# OpenTherm_Board_77X.net
KiCad netlist of a schematic drawn in EAGLE
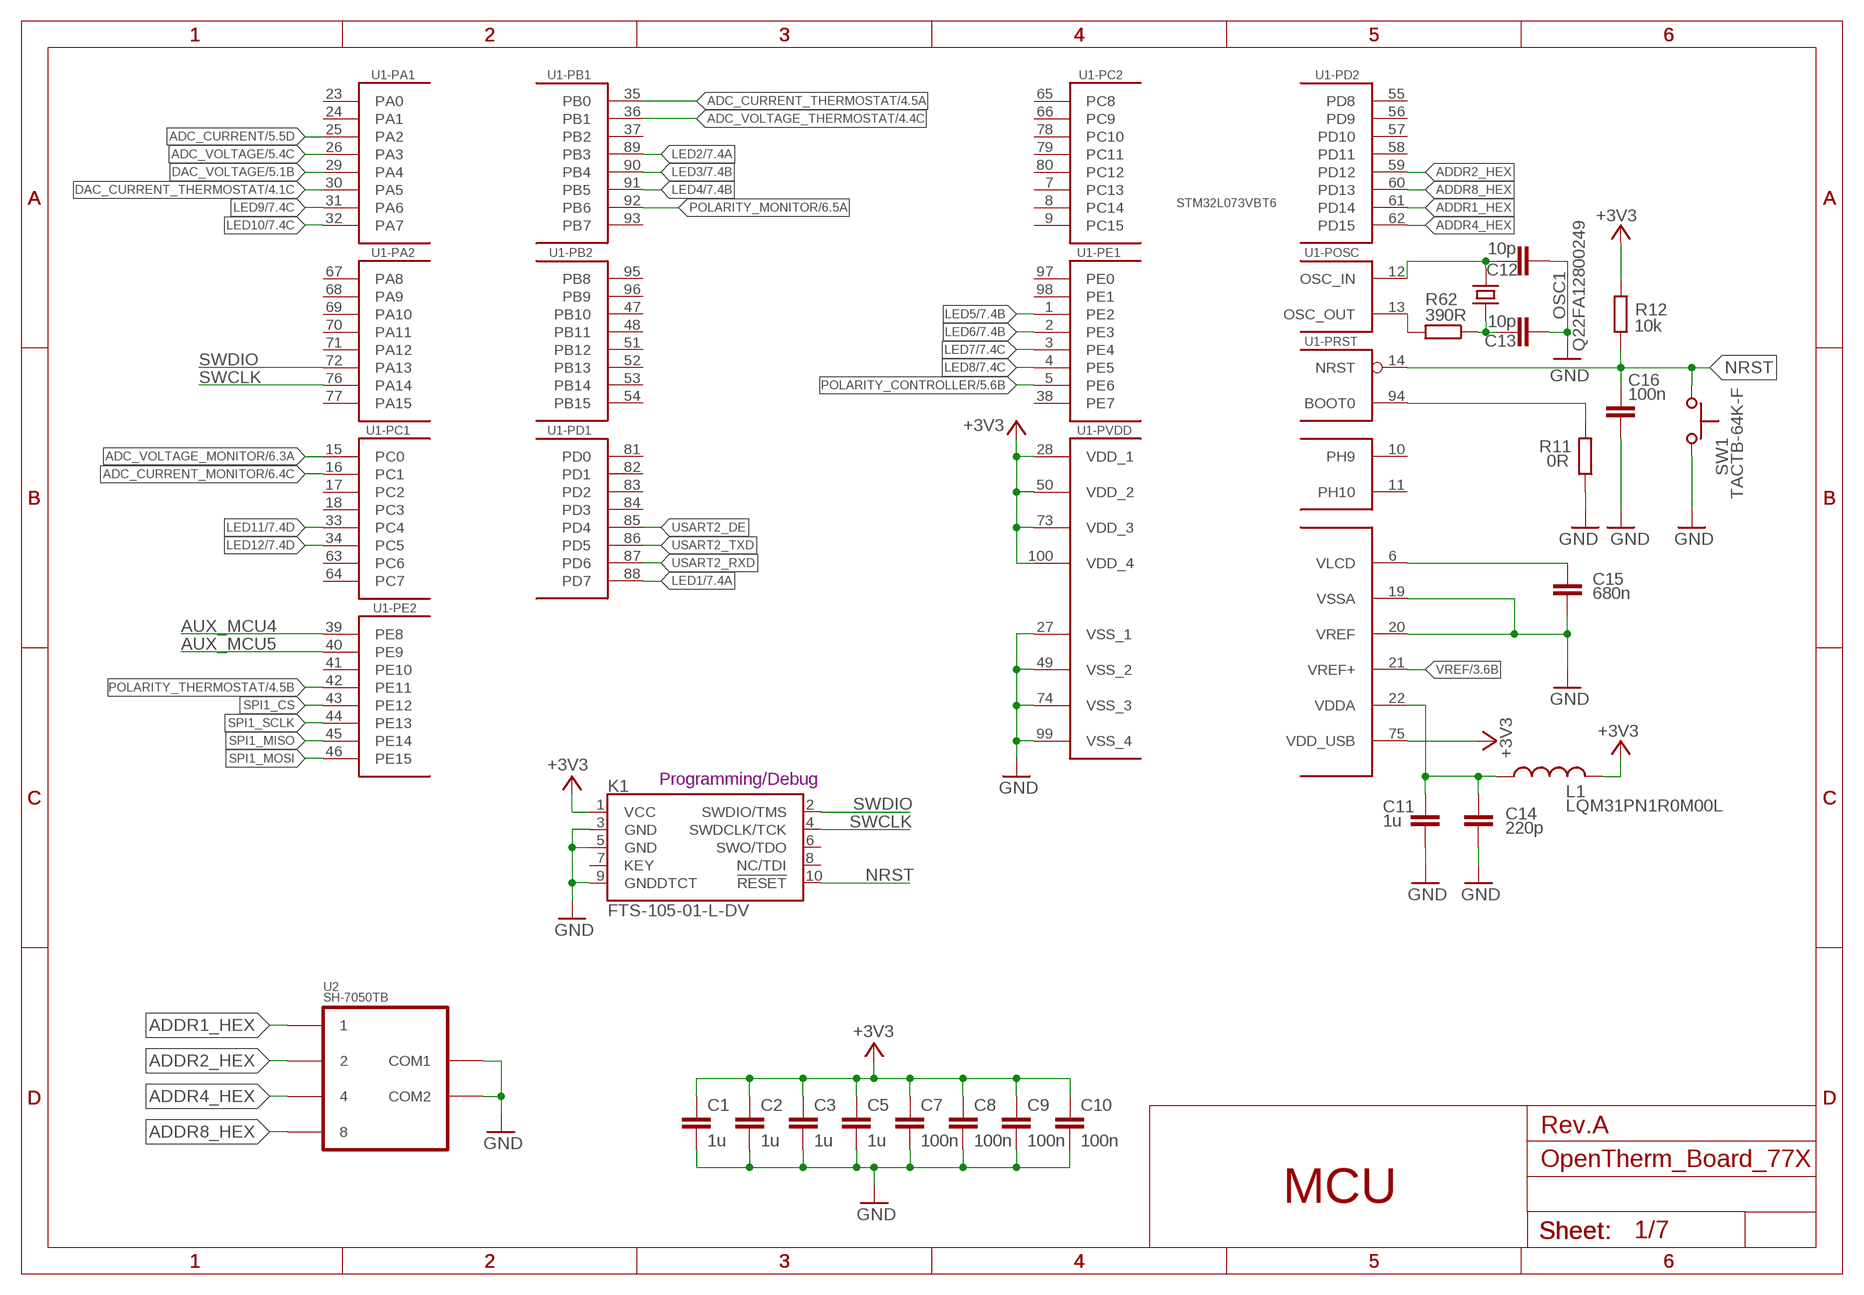
[diagram p0: schematic, sheet 1]
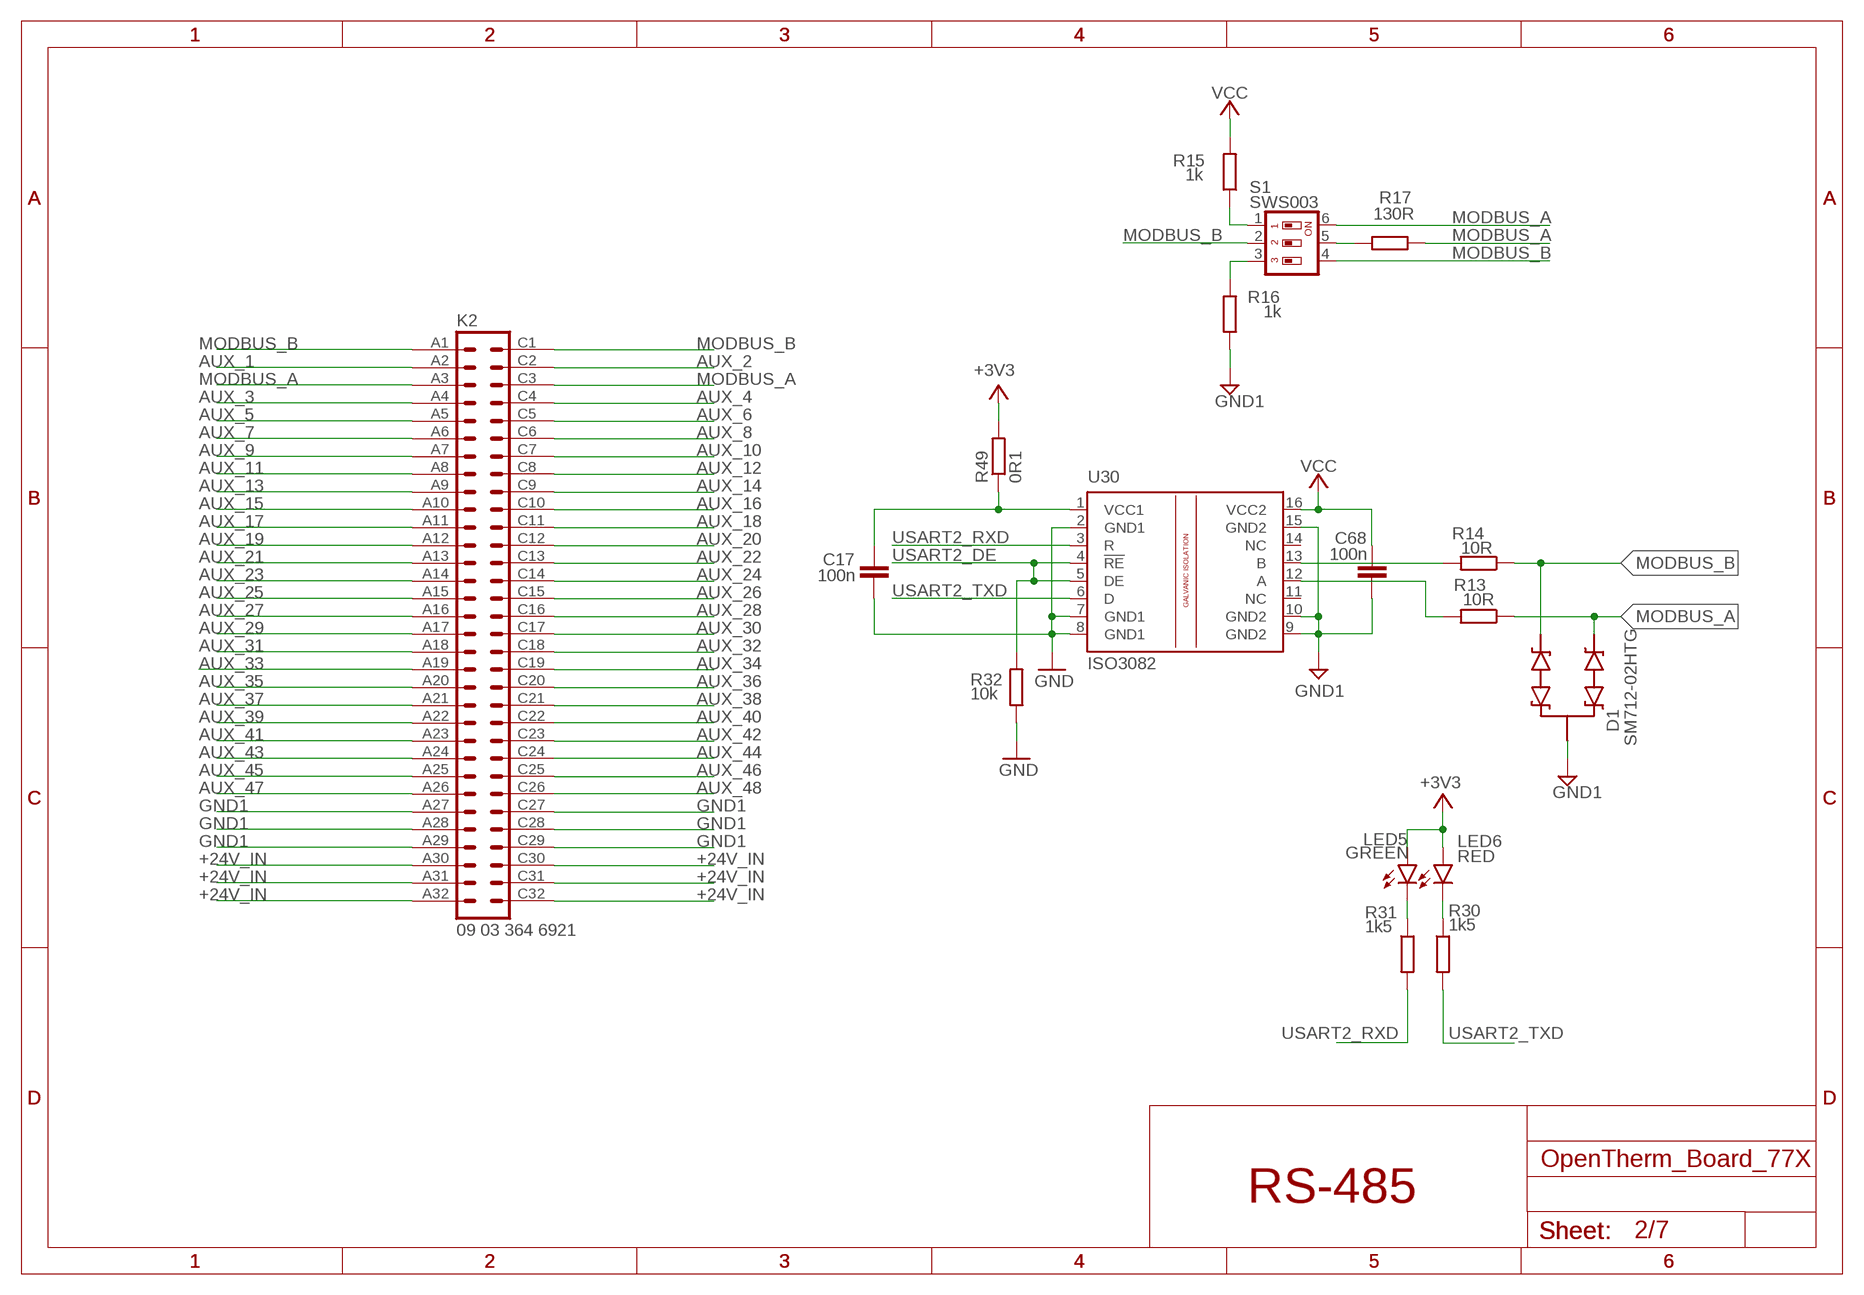
[diagram p1: schematic, sheet 2]
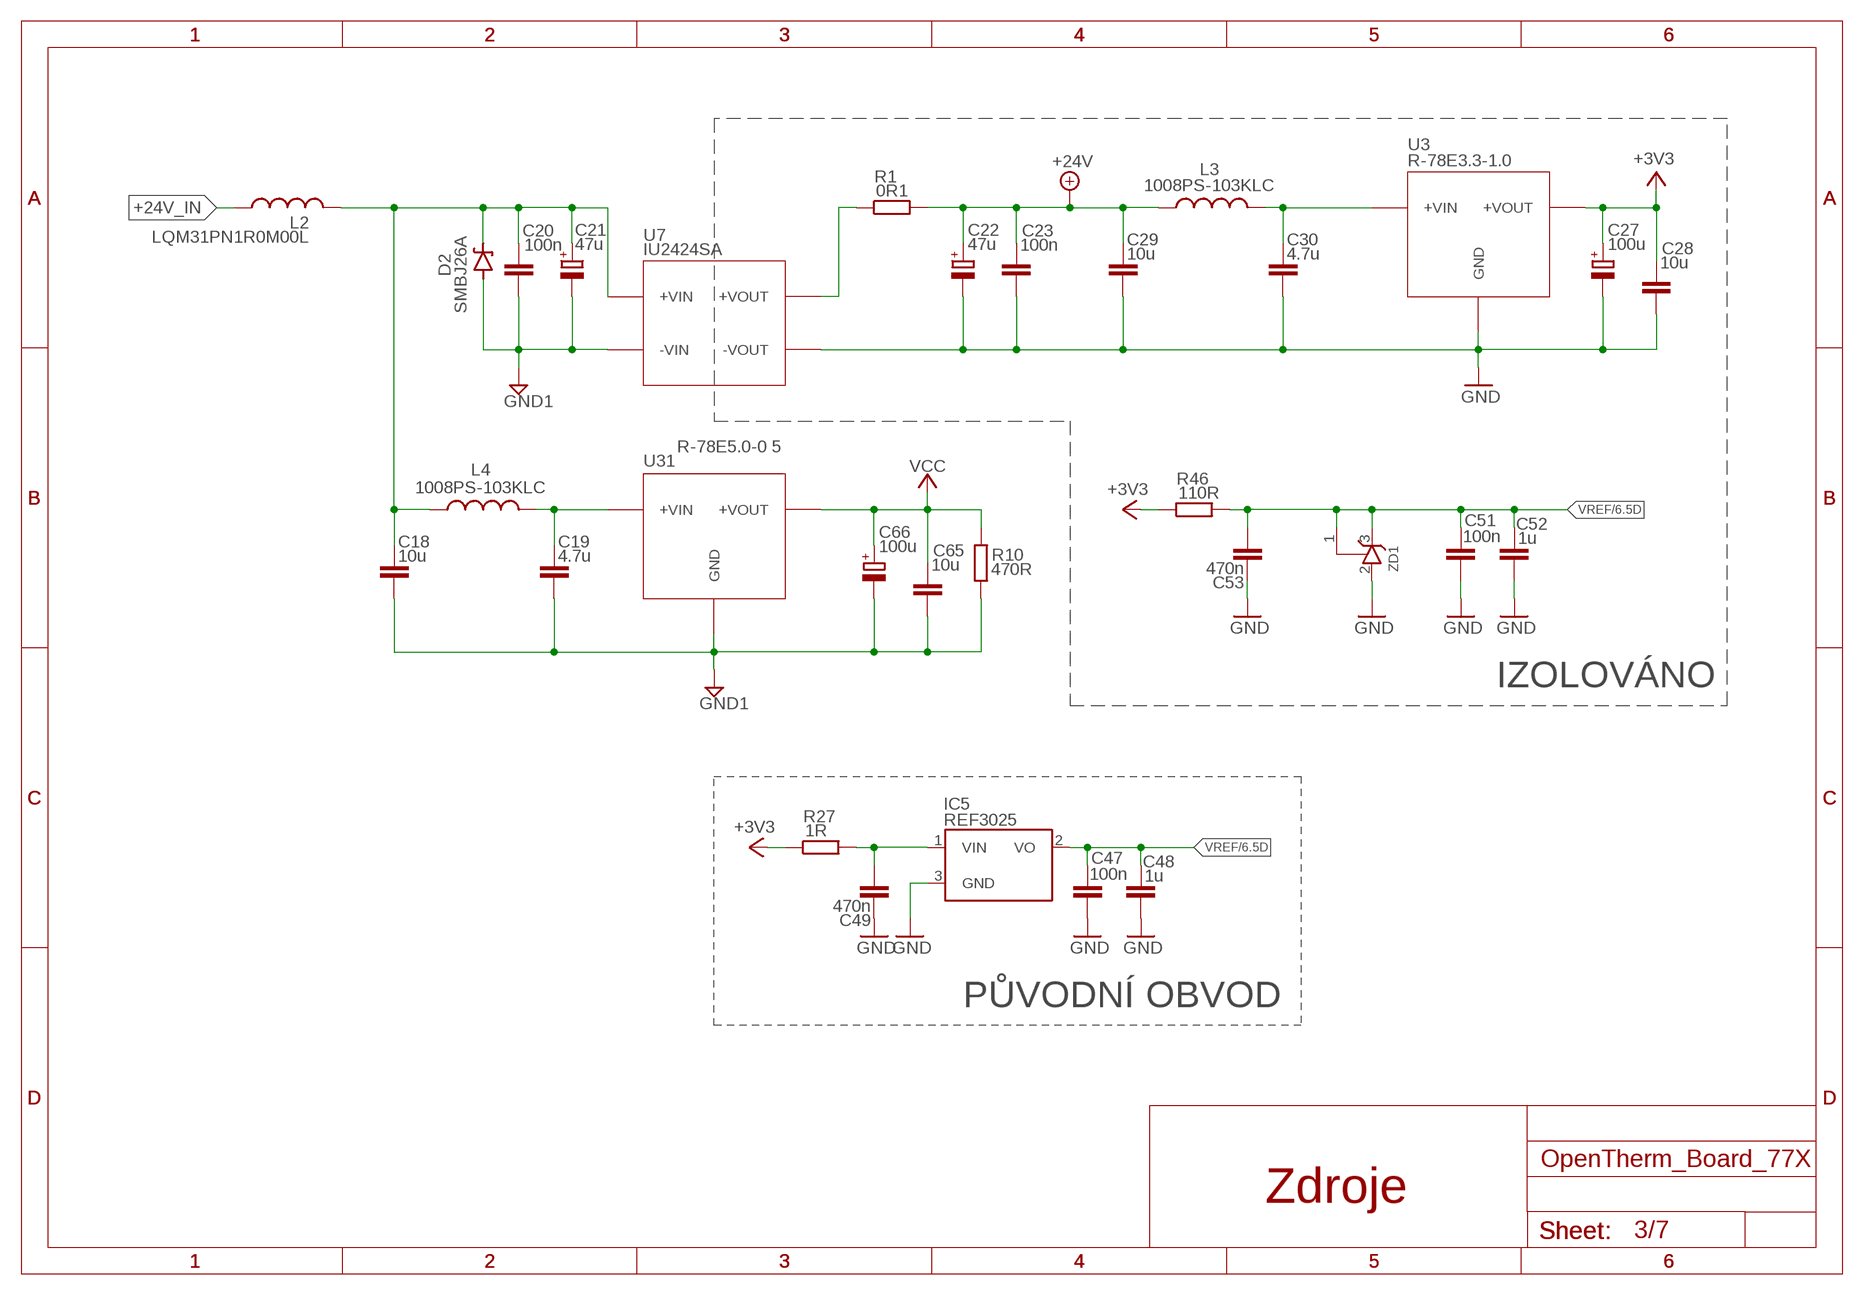
[diagram p2: schematic, sheet 3]
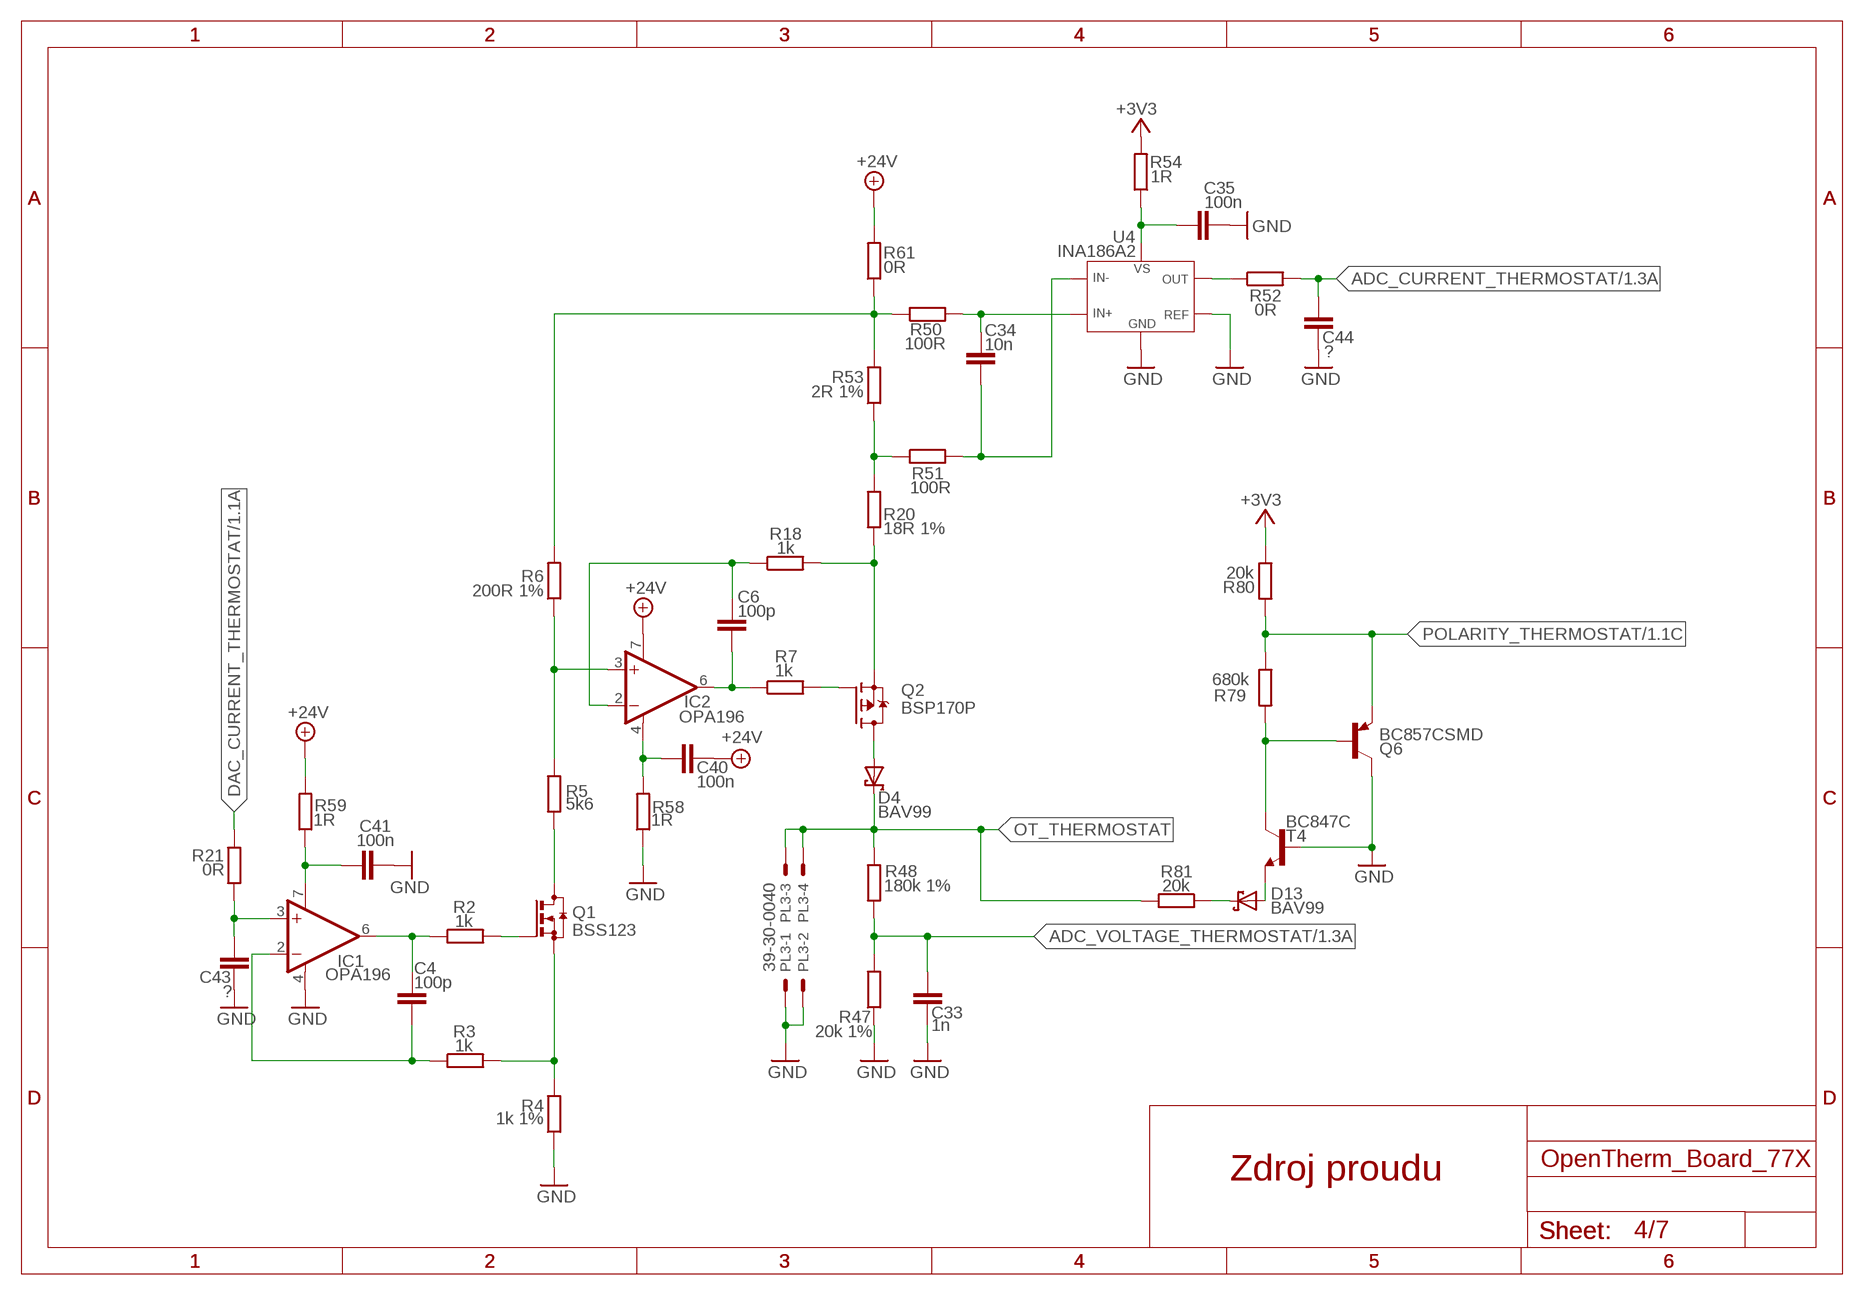
[diagram p3: schematic, sheet 4]
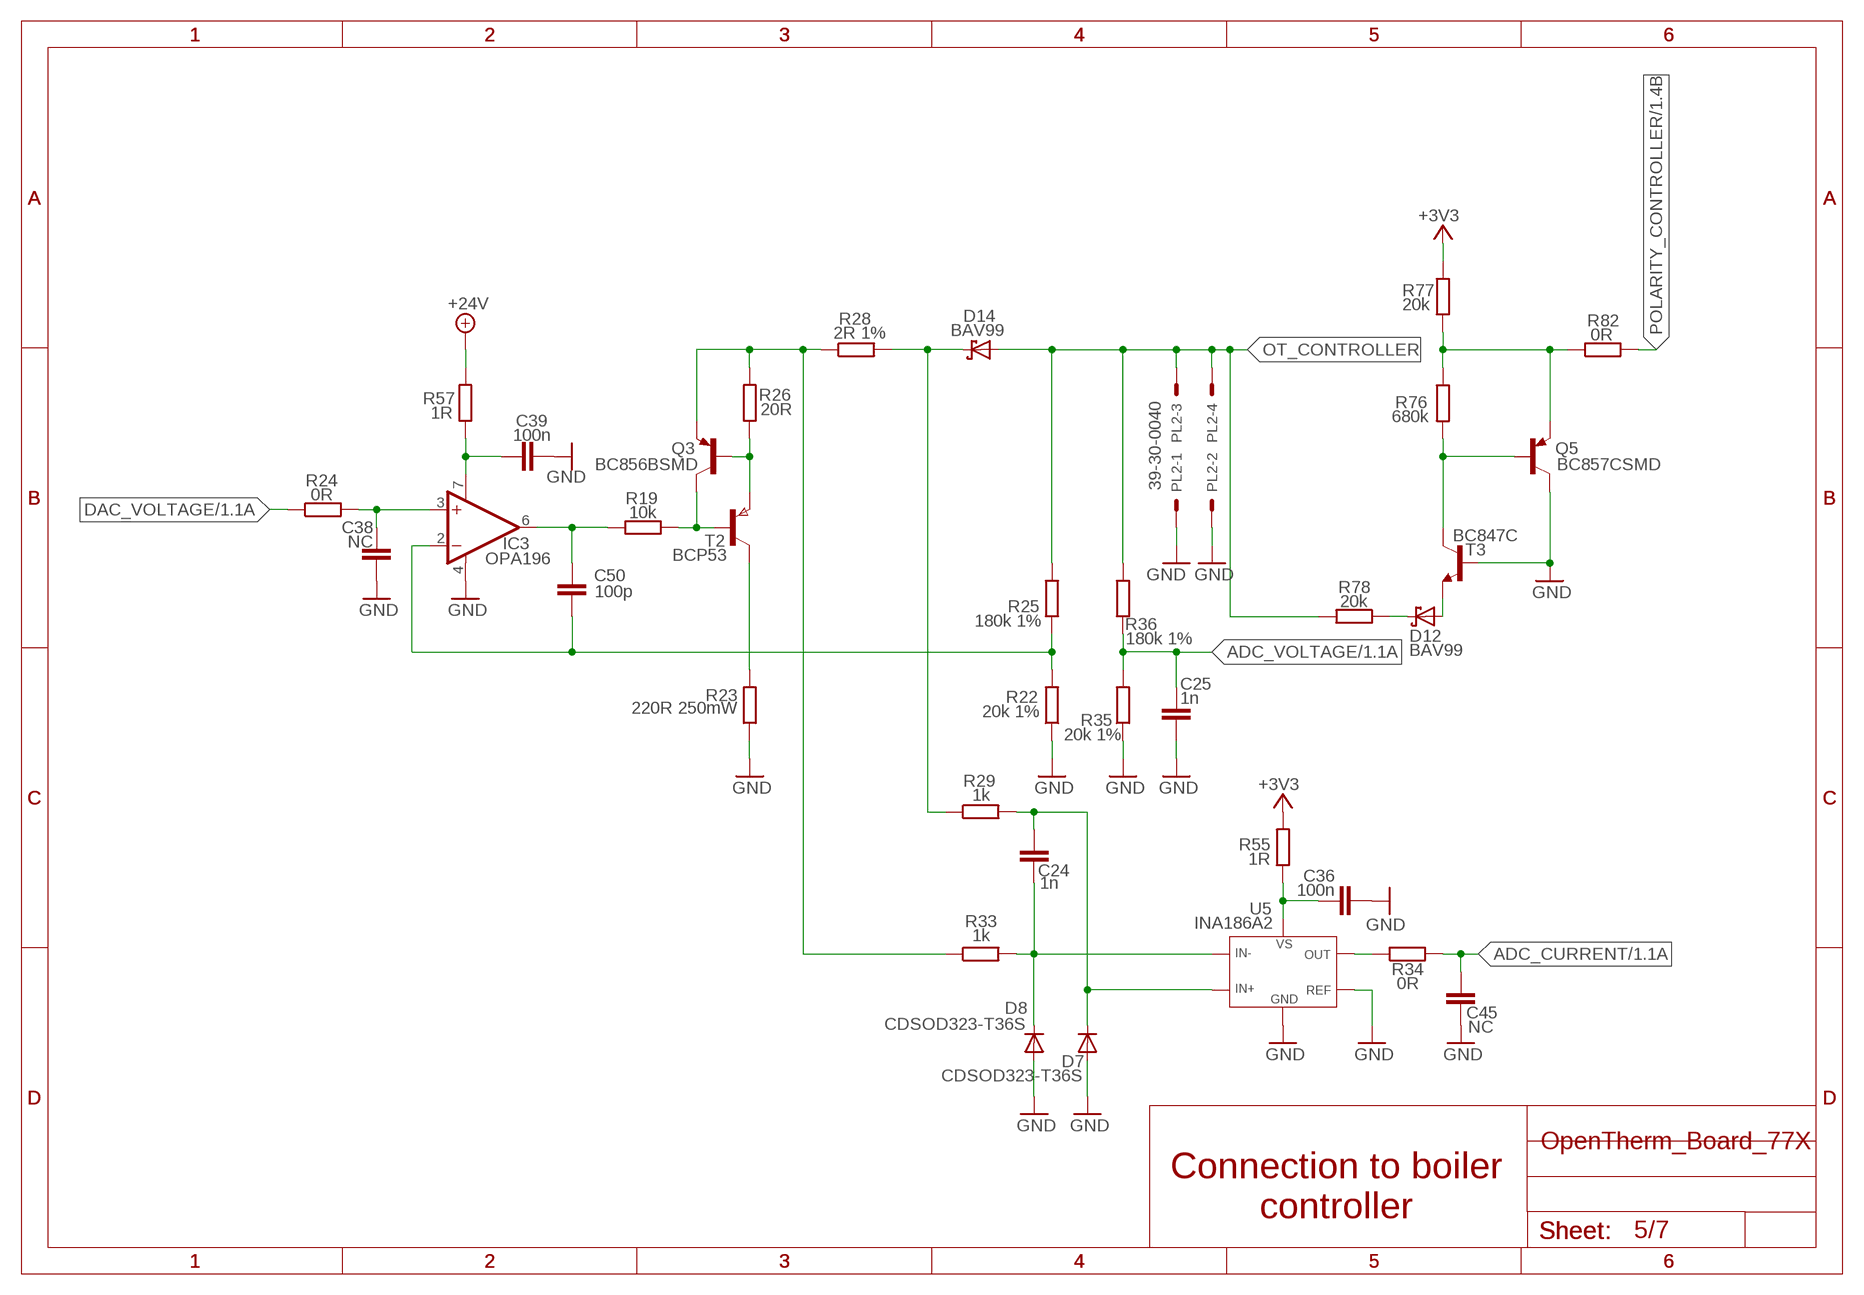
[diagram p4: schematic, sheet 5]
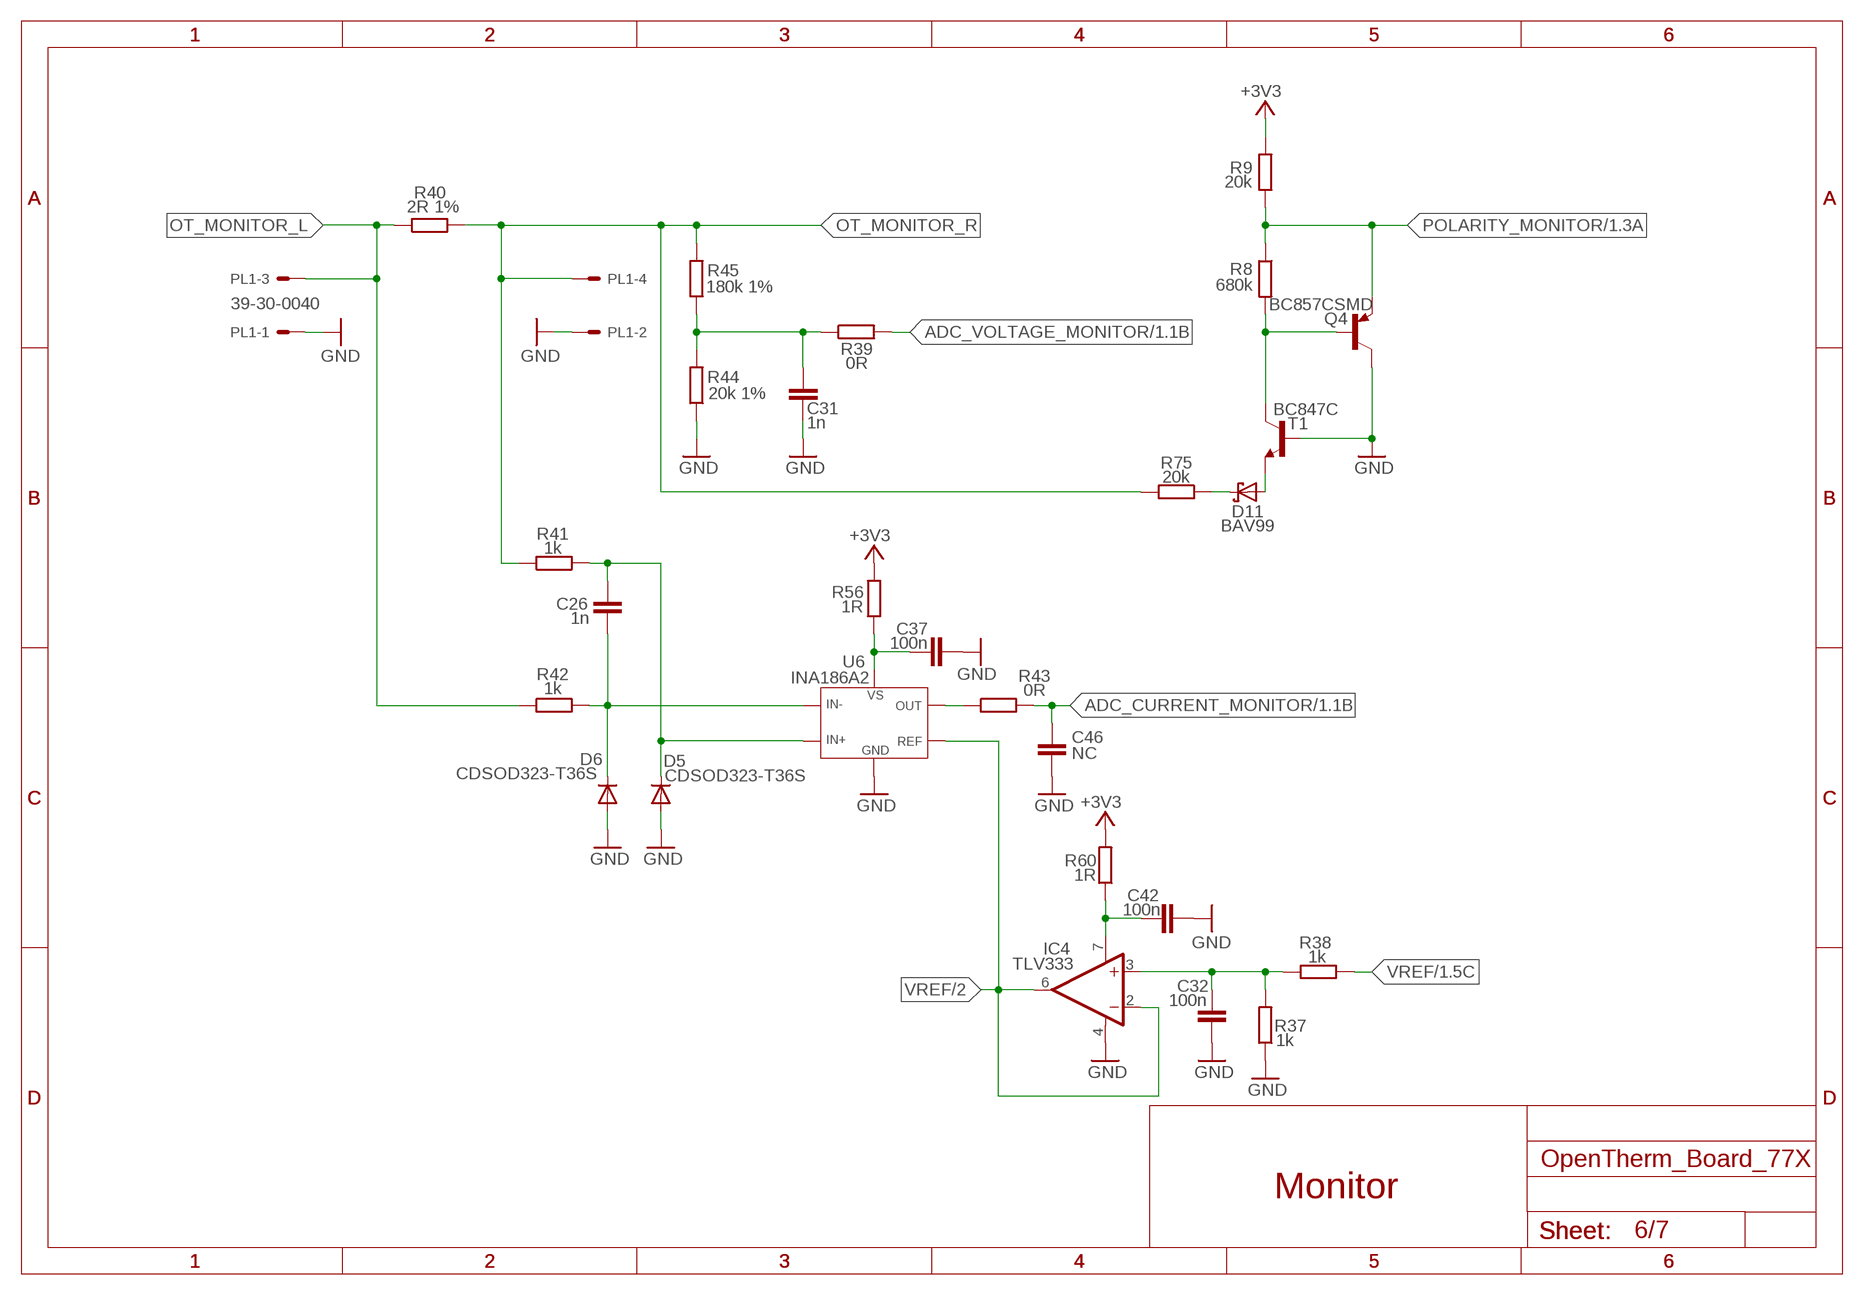
[diagram p5: schematic, sheet 6]
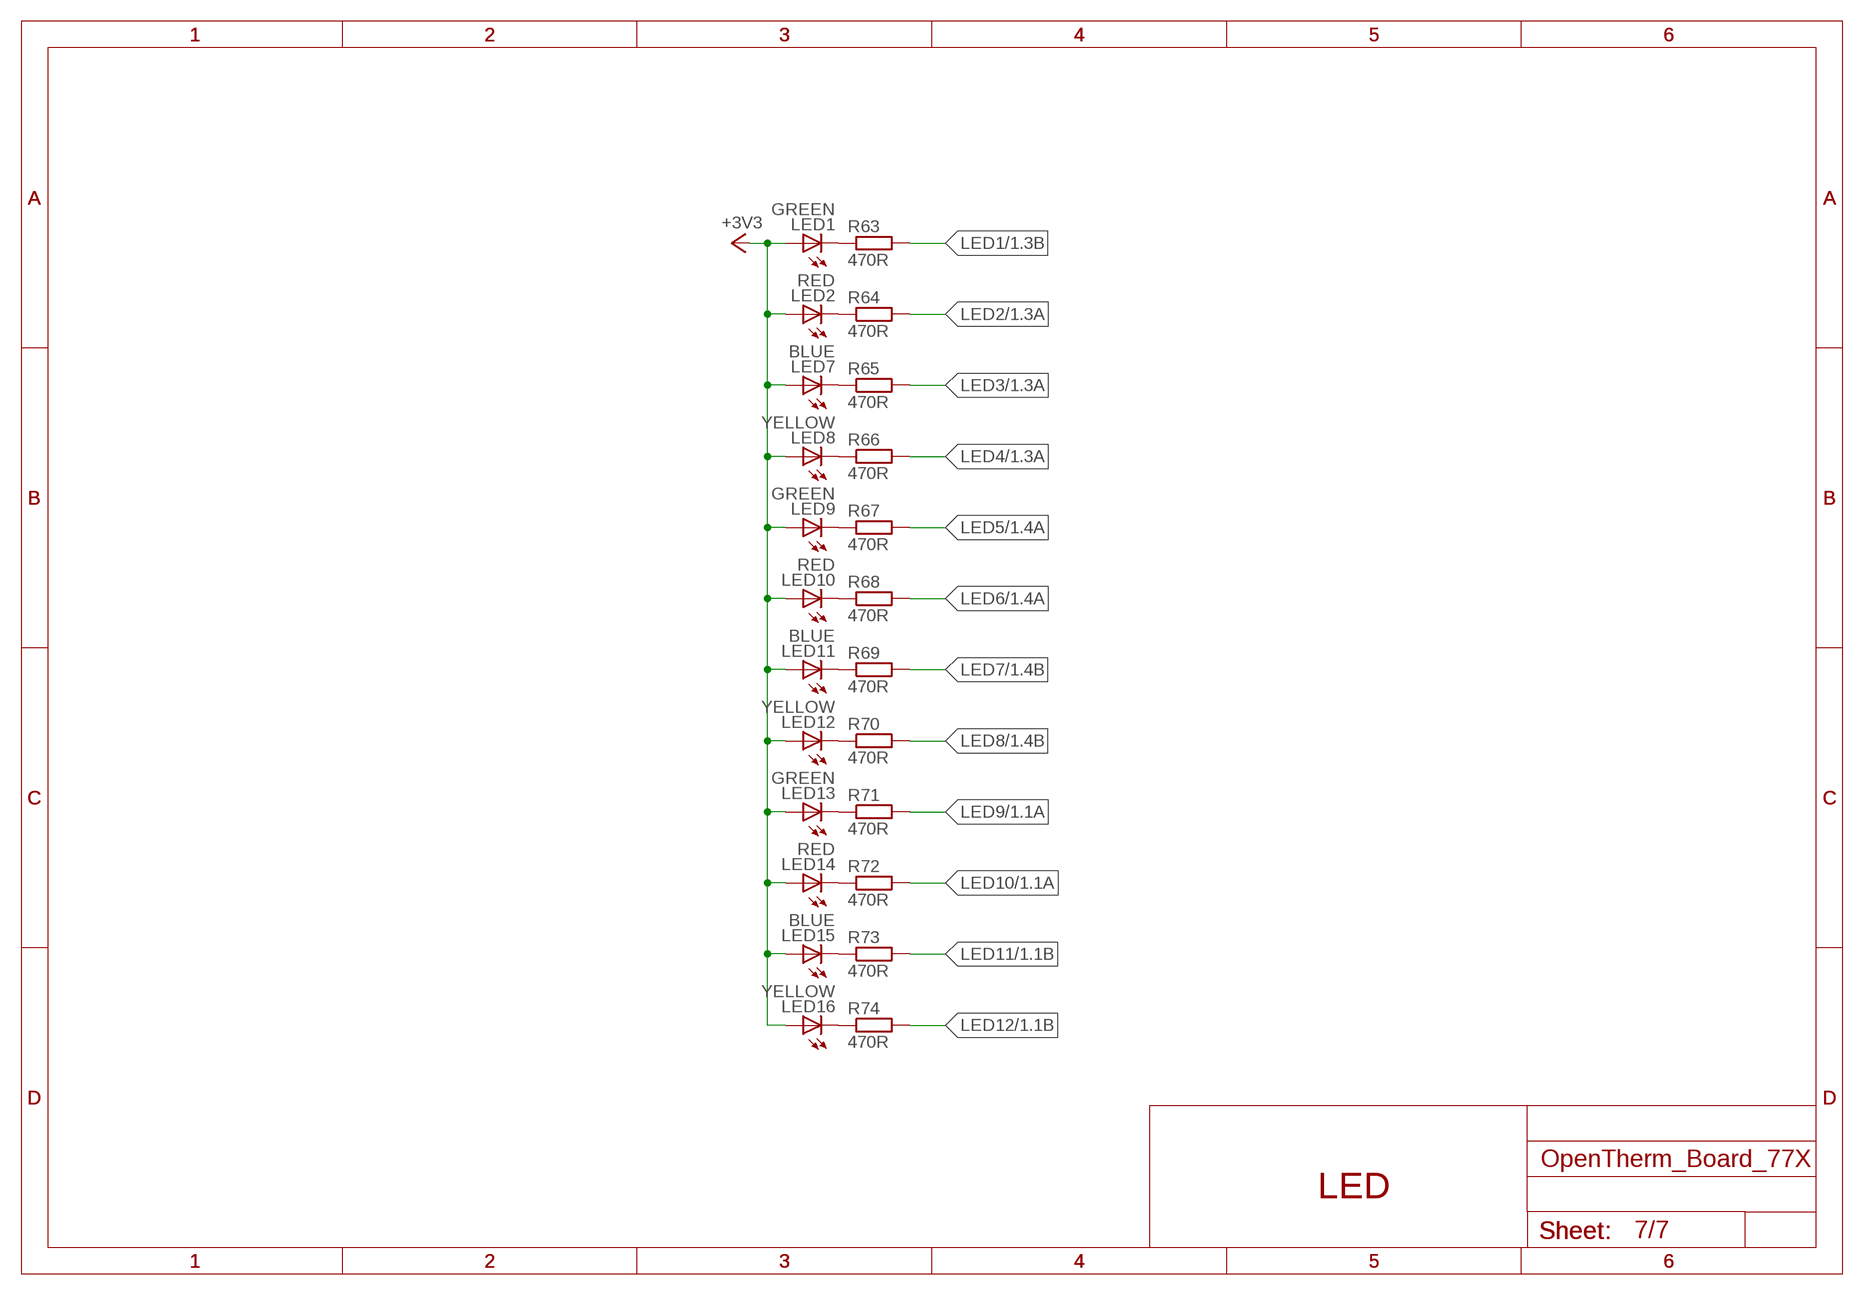
[diagram p6: schematic, sheet 7]

(export (version "E")
  (design (tool "Eeschema 10.0.6"))
  (components
    (comp (ref "C1")
      (value "1u")
      (footprint "eagle-import:C0805")
      (libsource (lib "eagle-import") (part "C-EUC0805"))
    )
    (comp (ref "C2")
      (value "1u")
      (footprint "eagle-import:C0805")
      (libsource (lib "eagle-import") (part "C-EUC0805"))
    )
    (comp (ref "C3")
      (value "1u")
      (footprint "eagle-import:C0805")
      (libsource (lib "eagle-import") (part "C-EUC0805"))
    )
    (comp (ref "C5")
      (value "1u")
      (footprint "eagle-import:C0805")
      (libsource (lib "eagle-import") (part "C-EUC0805"))
    )
    (comp (ref "C7")
      (value "100n")
      (footprint "eagle-import:C0603")
      (libsource (lib "eagle-import") (part "rcl_C-EUC0603"))
    )
    (comp (ref "C8")
      (value "100n")
      (footprint "eagle-import:C0603")
      (libsource (lib "eagle-import") (part "rcl_C-EUC0603"))
    )
    (comp (ref "C9")
      (value "100n")
      (footprint "eagle-import:C0603")
      (libsource (lib "eagle-import") (part "rcl_C-EUC0603"))
    )
    (comp (ref "C10")
      (value "100n")
      (footprint "eagle-import:C0603")
      (libsource (lib "eagle-import") (part "rcl_C-EUC0603"))
    )
    (comp (ref "C11")
      (value "1u")
      (footprint "eagle-import:C0805")
      (libsource (lib "eagle-import") (part "C-EUC0805"))
    )
    (comp (ref "C12")
      (value "10p")
      (footprint "eagle-import:C0603")
      (libsource (lib "eagle-import") (part "C-EUC0603"))
    )
    (comp (ref "C13")
      (value "10p")
      (footprint "eagle-import:C0603")
      (libsource (lib "eagle-import") (part "rcl_C-EUC0603"))
    )
    (comp (ref "C14")
      (value "220p")
      (footprint "eagle-import:C0603")
      (libsource (lib "eagle-import") (part "rcl_C-EUC0603"))
    )
    (comp (ref "C15")
      (value "680n")
      (footprint "eagle-import:C0603_1")
      (libsource (lib "eagle-import") (part "C-EU?C0603"))
    )
    (comp (ref "C16")
      (value "100n")
      (footprint "eagle-import:C0603")
      (libsource (lib "eagle-import") (part "rcl_C-EUC0603"))
    )
    (comp (ref "K1")
      (value "FTS-105-01-L-DV")
      (footprint "eagle-import:SAMTECH_FTSH-105-01")
      (libsource (lib "eagle-import") (part "CORTEX_DEBUG_SMD"))
    )
    (comp (ref "L1")
      (value "LQM31PN1R0M00L")
      (footprint "eagle-import:R1206")
      (libsource (lib "eagle-import") (part "L-US"))
    )
    (comp (ref "OSC1")
      (value "Q22FA12800249")
      (footprint "eagle-import:OSCILATOR")
      (libsource (lib "eagle-import") (part "Q22FA12800249"))
    )
    (comp (ref "R11")
      (value "0R")
      (footprint "eagle-import:R0603")
      (libsource (lib "eagle-import") (part "R-EU_R0603"))
    )
    (comp (ref "R12")
      (value "10k")
      (footprint "eagle-import:R0603")
      (libsource (lib "eagle-import") (part "R-EU_R0603"))
    )
    (comp (ref "R62")
      (value "390R")
      (footprint "eagle-import:R0603")
      (libsource (lib "eagle-import") (part "R-EU_R0603"))
    )
    (comp (ref "SW1")
      (value "TACTB-64K-F")
      (footprint "eagle-import:TACTB-64K-F")
      (libsource (lib "eagle-import") (part "TACTB-64K-F"))
    )
    (comp (ref "U1")
      (value "STM32L073VBT6")
      (footprint "eagle-import:TQFP100")
      (libsource (lib "eagle-import") (part "STM32L073VBT6"))
    )
    (comp (ref "U2")
      (value "SH-7050TB")
      (footprint "eagle-import:HEX_DEC")
      (libsource (lib "eagle-import") (part "SH-7050TB"))
    )
    (comp (ref "C26")
      (value "1n")
      (footprint "eagle-import:C0805")
      (libsource (lib "eagle-import") (part "C-EUC0805"))
    )
    (comp (ref "C31")
      (value "1n")
      (footprint "eagle-import:C0805")
      (libsource (lib "eagle-import") (part "C-EUC0805"))
    )
    (comp (ref "C32")
      (value "100n")
      (footprint "eagle-import:C0805")
      (libsource (lib "eagle-import") (part "C-EUC0805"))
    )
    (comp (ref "C37")
      (value "100n")
      (footprint "eagle-import:C0805")
      (libsource (lib "eagle-import") (part "C-EUC0805"))
    )
    (comp (ref "C42")
      (value "100n")
      (footprint "eagle-import:C0805")
      (libsource (lib "eagle-import") (part "C-EUC0805"))
    )
    (comp (ref "C46")
      (value "NC")
      (footprint "eagle-import:C0805")
      (libsource (lib "eagle-import") (part "C-EUC0805"))
    )
    (comp (ref "D5")
      (value "CDSOD323-T36S")
      (footprint "eagle-import:SOD323-W")
      (libsource (lib "eagle-import") (part "DIODE-SOD323-W"))
    )
    (comp (ref "D6")
      (value "CDSOD323-T36S")
      (footprint "eagle-import:SOD323-W")
      (libsource (lib "eagle-import") (part "DIODE-SOD323-W"))
    )
    (comp (ref "D11")
      (value "BAV99")
      (footprint "eagle-import:SOT23")
      (libsource (lib "eagle-import") (part "BAS70"))
    )
    (comp (ref "IC4")
      (value "TLV333")
      (footprint "eagle-import:SO08")
      (fields (field (name "MPN") "OPA340UA"))
      (libsource (lib "eagle-import") (part "OPA340U"))
    )
    (comp (ref "PL1")
      (value "39-30-0040")
      (footprint "eagle-import:5569-4")
      (fields (field (name "OC_FARNELL") "1697133"))
      (libsource (lib "eagle-import") (part "555X-4H"))
    )
    (comp (ref "Q4")
      (value "BC857CSMD")
      (footprint "eagle-import:SOT23-BEC")
      (libsource (lib "eagle-import") (part "BC857SMDC"))
    )
    (comp (ref "R8")
      (value "680k")
      (footprint "eagle-import:R0805")
      (libsource (lib "eagle-import") (part "R-EU_R0805"))
    )
    (comp (ref "R9")
      (value "20k")
      (footprint "eagle-import:R0805")
      (libsource (lib "eagle-import") (part "R-EU_R0805"))
    )
    (comp (ref "R37")
      (value "1k")
      (footprint "eagle-import:R1206")
      (libsource (lib "eagle-import") (part "R-EU_R1206"))
    )
    (comp (ref "R38")
      (value "1k")
      (footprint "eagle-import:R1206")
      (libsource (lib "eagle-import") (part "R-EU_R1206"))
    )
    (comp (ref "R39")
      (value "0R")
      (footprint "eagle-import:R1206")
      (libsource (lib "eagle-import") (part "R-EU_R1206"))
    )
    (comp (ref "R40")
      (value "2R 1%")
      (footprint "eagle-import:R1206")
      (libsource (lib "eagle-import") (part "R-EU_R1206"))
    )
    (comp (ref "R41")
      (value "1k")
      (footprint "eagle-import:R0805")
      (libsource (lib "eagle-import") (part "R-EU_R0805"))
    )
    (comp (ref "R42")
      (value "1k")
      (footprint "eagle-import:R0805")
      (libsource (lib "eagle-import") (part "R-EU_R0805"))
    )
    (comp (ref "R43")
      (value "0R")
      (footprint "eagle-import:R1206")
      (libsource (lib "eagle-import") (part "R-EU_R1206"))
    )
    (comp (ref "R44")
      (value "20k 1%")
      (footprint "eagle-import:R0805")
      (libsource (lib "eagle-import") (part "R-EU_R0805"))
    )
    (comp (ref "R45")
      (value "180k 1%")
      (footprint "eagle-import:R0805")
      (libsource (lib "eagle-import") (part "R-EU_R0805"))
    )
    (comp (ref "R56")
      (value "1R")
      (footprint "eagle-import:R0805")
      (libsource (lib "eagle-import") (part "R-EU_R0805"))
    )
    (comp (ref "R60")
      (value "1R")
      (footprint "eagle-import:R0805")
      (libsource (lib "eagle-import") (part "R-EU_R0805"))
    )
    (comp (ref "R75")
      (value "20k")
      (footprint "eagle-import:R0805")
      (libsource (lib "eagle-import") (part "R-EU_R0805"))
    )
    (comp (ref "T1")
      (value "BC847C")
      (footprint "eagle-import:SOT23")
      (libsource (lib "eagle-import") (part "BC847"))
    )
    (comp (ref "U6")
      (value "INA186A2")
      (footprint "eagle-import:SC70-6L")
      (libsource (lib "eagle-import") (part "INA186A2"))
    )
    (comp (ref "C18")
      (value "10u")
      (footprint "eagle-import:C1206")
      (libsource (lib "eagle-import") (part "C-EUC1206"))
    )
    (comp (ref "C19")
      (value "4.7u")
      (footprint "eagle-import:C1206")
      (libsource (lib "eagle-import") (part "C-EUC1206"))
    )
    (comp (ref "C20")
      (value "100n")
      (footprint "eagle-import:C1206")
      (libsource (lib "eagle-import") (part "C-EUC1206"))
    )
    (comp (ref "C21")
      (value "47u")
      (footprint "eagle-import:E3,5-8")
      (libsource (lib "eagle-import") (part "CPOL-EUE3.5-8"))
    )
    (comp (ref "C22")
      (value "47u")
      (footprint "eagle-import:153CLV-0810")
      (libsource (lib "eagle-import") (part "rcl@1_CPOL-EU153CLV-0810"))
    )
    (comp (ref "C23")
      (value "100n")
      (footprint "eagle-import:C0805")
      (libsource (lib "eagle-import") (part "C-EUC0805"))
    )
    (comp (ref "C27")
      (value "100u")
      (footprint "eagle-import:153CLV-0605")
      (libsource (lib "eagle-import") (part "CPOL-EU153CLV-0605"))
    )
    (comp (ref "C28")
      (value "10u")
      (footprint "eagle-import:C1206")
      (libsource (lib "eagle-import") (part "C-EUC1206"))
    )
    (comp (ref "C29")
      (value "10u")
      (footprint "eagle-import:C1206")
      (libsource (lib "eagle-import") (part "C-EUC1206"))
    )
    (comp (ref "C30")
      (value "4.7u")
      (footprint "eagle-import:C1206")
      (libsource (lib "eagle-import") (part "C-EUC1206"))
    )
    (comp (ref "C47")
      (value "100n")
      (footprint "eagle-import:C0805")
      (libsource (lib "eagle-import") (part "C-EUC0805"))
    )
    (comp (ref "C48")
      (value "1u")
      (footprint "eagle-import:C0805")
      (libsource (lib "eagle-import") (part "C-EUC0805"))
    )
    (comp (ref "C49")
      (value "470n")
      (footprint "eagle-import:C0805")
      (libsource (lib "eagle-import") (part "C-EUC0805"))
    )
    (comp (ref "C51")
      (value "100n")
      (footprint "eagle-import:C0805")
      (libsource (lib "eagle-import") (part "C-EUC0805"))
    )
    (comp (ref "C52")
      (value "1u")
      (footprint "eagle-import:C0805")
      (libsource (lib "eagle-import") (part "C-EUC0805"))
    )
    (comp (ref "C53")
      (value "470n")
      (footprint "eagle-import:C0805")
      (libsource (lib "eagle-import") (part "C-EUC0805"))
    )
    (comp (ref "C65")
      (value "10u")
      (footprint "eagle-import:C1206")
      (libsource (lib "eagle-import") (part "C-EUC1206"))
    )
    (comp (ref "C66")
      (value "100u")
      (footprint "eagle-import:153CLV-0605")
      (libsource (lib "eagle-import") (part "CPOL-EU153CLV-0605"))
    )
    (comp (ref "D2")
      (value "SMBJ26A")
      (footprint "eagle-import:SMB")
      (libsource (lib "eagle-import") (part "SMBJ26A"))
    )
    (comp (ref "IC5")
      (value "REF3025")
      (footprint "eagle-import:SOT23")
      (libsource (lib "eagle-import") (part "MC15TT25"))
    )
    (comp (ref "L2")
      (value "LQM31PN1R0M00L")
      (footprint "eagle-import:R1206")
      (libsource (lib "eagle-import") (part "L-US"))
    )
    (comp (ref "L3")
      (value "1008PS-103KLC")
      (footprint "eagle-import:L1812")
      (libsource (lib "eagle-import") (part "L-US?{colon}1L1812"))
    )
    (comp (ref "L4")
      (value "1008PS-103KLC")
      (footprint "eagle-import:L1812")
      (libsource (lib "eagle-import") (part "L-US?{colon}1L1812"))
    )
    (comp (ref "R1")
      (value "0R1")
      (footprint "eagle-import:R1206")
      (libsource (lib "eagle-import") (part "R-EU_R1206"))
    )
    (comp (ref "R10")
      (value "470R")
      (footprint "eagle-import:R1206")
      (libsource (lib "eagle-import") (part "R-EU_R1206"))
    )
    (comp (ref "R27")
      (value "1R")
      (footprint "eagle-import:R0805")
      (libsource (lib "eagle-import") (part "R-EU_R0805"))
    )
    (comp (ref "R46")
      (value "110R")
      (footprint "eagle-import:R0805")
      (libsource (lib "eagle-import") (part "R-EU_R0805"))
    )
    (comp (ref "U3")
      (value "R-78E3.3-1.0")
      (footprint "eagle-import:R-78E-0.5")
      (libsource (lib "eagle-import") (part "R-78E-0.5"))
    )
    (comp (ref "U7")
      (value "IU2424SA")
      (footprint "eagle-import:IU2405SA")
      (libsource (lib "eagle-import") (part "IU2405SA"))
    )
    (comp (ref "U31")
      (value "R-78E5.0-0 5")
      (footprint "eagle-import:R-78E-0.5")
      (libsource (lib "eagle-import") (part "R-78E-0.5"))
    )
    (comp (ref "ZD1")
      (value "TL431INLINE")
      (footprint "eagle-import:TO92-R")
      (libsource (lib "eagle-import") (part "TL431INLINE"))
    )
    (comp (ref "C24")
      (value "1n")
      (footprint "eagle-import:C0805")
      (libsource (lib "eagle-import") (part "C-EUC0805"))
    )
    (comp (ref "C25")
      (value "1n")
      (footprint "eagle-import:C0805")
      (libsource (lib "eagle-import") (part "C-EUC0805"))
    )
    (comp (ref "C36")
      (value "100n")
      (footprint "eagle-import:C0805")
      (libsource (lib "eagle-import") (part "C-EUC0805"))
    )
    (comp (ref "C38")
      (value "NC")
      (footprint "eagle-import:C0805")
      (libsource (lib "eagle-import") (part "C-EUC0805"))
    )
    (comp (ref "C39")
      (value "100n")
      (footprint "eagle-import:C0805")
      (libsource (lib "eagle-import") (part "C-EUC0805"))
    )
    (comp (ref "C45")
      (value "NC")
      (footprint "eagle-import:C0805")
      (libsource (lib "eagle-import") (part "C-EUC0805"))
    )
    (comp (ref "C50")
      (value "100p")
      (footprint "eagle-import:C0805")
      (libsource (lib "eagle-import") (part "C-EUC0805"))
    )
    (comp (ref "D7")
      (value "CDSOD323-T36S")
      (footprint "eagle-import:SOD323-W")
      (libsource (lib "eagle-import") (part "DIODE-SOD323-W"))
    )
    (comp (ref "D8")
      (value "CDSOD323-T36S")
      (footprint "eagle-import:SOD323-W")
      (libsource (lib "eagle-import") (part "DIODE-SOD323-W"))
    )
    (comp (ref "D12")
      (value "BAV99")
      (footprint "eagle-import:SOT23")
      (libsource (lib "eagle-import") (part "BAS70"))
    )
    (comp (ref "D14")
      (value "BAV99")
      (footprint "eagle-import:SOT23")
      (libsource (lib "eagle-import") (part "BAS70"))
    )
    (comp (ref "IC3")
      (value "OPA196")
      (footprint "eagle-import:SO08")
      (fields (field (name "MPN") "OPA340UA"))
      (libsource (lib "eagle-import") (part "OPA340U"))
    )
    (comp (ref "PL2")
      (value "39-30-0040")
      (footprint "eagle-import:5569-4")
      (fields (field (name "OC_FARNELL") "1697133"))
      (libsource (lib "eagle-import") (part "555X-4H"))
    )
    (comp (ref "Q3")
      (value "BC856BSMD")
      (footprint "eagle-import:SOT23-BEC")
      (libsource (lib "eagle-import") (part "BC856SMDB"))
    )
    (comp (ref "Q5")
      (value "BC857CSMD")
      (footprint "eagle-import:SOT23-BEC")
      (libsource (lib "eagle-import") (part "BC857SMDC"))
    )
    (comp (ref "R19")
      (value "10k")
      (footprint "eagle-import:R0805")
      (libsource (lib "eagle-import") (part "R-EU_R0805"))
    )
    (comp (ref "R22")
      (value "20k 1%")
      (footprint "eagle-import:R0805")
      (libsource (lib "eagle-import") (part "R-EU_R0805"))
    )
    (comp (ref "R23")
      (value "220R 250mW")
      (footprint "eagle-import:R1206")
      (libsource (lib "eagle-import") (part "R-EU_R1206"))
    )
    (comp (ref "R24")
      (value "0R")
      (footprint "eagle-import:R1206")
      (libsource (lib "eagle-import") (part "R-EU_R1206"))
    )
    (comp (ref "R25")
      (value "180k 1%")
      (footprint "eagle-import:R0805")
      (libsource (lib "eagle-import") (part "R-EU_R0805"))
    )
    (comp (ref "R26")
      (value "20R")
      (footprint "eagle-import:R1206")
      (libsource (lib "eagle-import") (part "R-EU_R1206"))
    )
    (comp (ref "R28")
      (value "2R 1%")
      (footprint "eagle-import:R1206")
      (libsource (lib "eagle-import") (part "R-EU_R1206"))
    )
    (comp (ref "R29")
      (value "1k")
      (footprint "eagle-import:R0805")
      (libsource (lib "eagle-import") (part "R-EU_R0805"))
    )
    (comp (ref "R33")
      (value "1k")
      (footprint "eagle-import:R0805")
      (libsource (lib "eagle-import") (part "R-EU_R0805"))
    )
    (comp (ref "R34")
      (value "0R")
      (footprint "eagle-import:R1206")
      (libsource (lib "eagle-import") (part "R-EU_R1206"))
    )
    (comp (ref "R35")
      (value "20k 1%")
      (footprint "eagle-import:R0805")
      (libsource (lib "eagle-import") (part "R-EU_R0805"))
    )
    (comp (ref "R36")
      (value "180k 1%")
      (footprint "eagle-import:R0805")
      (libsource (lib "eagle-import") (part "R-EU_R0805"))
    )
    (comp (ref "R55")
      (value "1R")
      (footprint "eagle-import:R0805")
      (libsource (lib "eagle-import") (part "R-EU_R0805"))
    )
    (comp (ref "R57")
      (value "1R")
      (footprint "eagle-import:R1206")
      (libsource (lib "eagle-import") (part "R-EU_R1206"))
    )
    (comp (ref "R76")
      (value "680k")
      (footprint "eagle-import:R0805")
      (libsource (lib "eagle-import") (part "R-EU_R0805"))
    )
    (comp (ref "R77")
      (value "20k")
      (footprint "eagle-import:R0805")
      (libsource (lib "eagle-import") (part "R-EU_R0805"))
    )
    (comp (ref "R78")
      (value "20k")
      (footprint "eagle-import:R0805")
      (libsource (lib "eagle-import") (part "R-EU_R0805"))
    )
    (comp (ref "R82")
      (value "0R")
      (footprint "eagle-import:R1206")
      (libsource (lib "eagle-import") (part "R-EU_R1206"))
    )
    (comp (ref "T2")
      (value "BCP53")
      (footprint "eagle-import:SOT223")
      (fields (field (name "MPN") "DJT4030P-13"))
      (libsource (lib "eagle-import") (part "PNPSOT223"))
    )
    (comp (ref "T3")
      (value "BC847C")
      (footprint "eagle-import:SOT23")
      (libsource (lib "eagle-import") (part "BC847"))
    )
    (comp (ref "U5")
      (value "INA186A2")
      (footprint "eagle-import:SC70-6L")
      (libsource (lib "eagle-import") (part "INA186A2"))
    )
    (comp (ref "C4")
      (value "100p")
      (footprint "eagle-import:C0805")
      (libsource (lib "eagle-import") (part "C-EUC0805"))
    )
    (comp (ref "C6")
      (value "100p")
      (footprint "eagle-import:C0805")
      (libsource (lib "eagle-import") (part "C-EUC0805"))
    )
    (comp (ref "C33")
      (value "1n")
      (footprint "eagle-import:C0805")
      (libsource (lib "eagle-import") (part "C-EUC0805"))
    )
    (comp (ref "C34")
      (value "10n")
      (footprint "eagle-import:C0805")
      (libsource (lib "eagle-import") (part "C-EUC0805"))
    )
    (comp (ref "C35")
      (value "100n")
      (footprint "eagle-import:C0805")
      (libsource (lib "eagle-import") (part "C-EUC0805"))
    )
    (comp (ref "C40")
      (value "100n")
      (footprint "eagle-import:C0805")
      (libsource (lib "eagle-import") (part "C-EUC0805"))
    )
    (comp (ref "C41")
      (value "100n")
      (footprint "eagle-import:C0805")
      (libsource (lib "eagle-import") (part "C-EUC0805"))
    )
    (comp (ref "C43")
      (value "?")
      (footprint "eagle-import:C0805")
      (libsource (lib "eagle-import") (part "C-EUC0805"))
    )
    (comp (ref "C44")
      (value "?")
      (footprint "eagle-import:C0805")
      (libsource (lib "eagle-import") (part "C-EUC0805"))
    )
    (comp (ref "D4")
      (value "BAV99")
      (footprint "eagle-import:SOT23")
      (libsource (lib "eagle-import") (part "BAS70"))
    )
    (comp (ref "D13")
      (value "BAV99")
      (footprint "eagle-import:SOT23")
      (libsource (lib "eagle-import") (part "BAS70"))
    )
    (comp (ref "IC1")
      (value "OPA196")
      (footprint "eagle-import:SO08")
      (fields (field (name "MPN") "OPA340UA"))
      (libsource (lib "eagle-import") (part "OPA340U"))
    )
    (comp (ref "IC2")
      (value "OPA196")
      (footprint "eagle-import:SO08")
      (fields (field (name "MPN") "OPA340UA"))
      (libsource (lib "eagle-import") (part "OPA340U"))
    )
    (comp (ref "PL3")
      (value "39-30-0040")
      (footprint "eagle-import:5569-4")
      (fields (field (name "OC_FARNELL") "1697133"))
      (libsource (lib "eagle-import") (part "555X-4H"))
    )
    (comp (ref "Q1")
      (value "BSS123")
      (footprint "eagle-import:SOT23")
      (libsource (lib "eagle-import") (part "BSS123"))
    )
    (comp (ref "Q2")
      (value "BSP170P")
      (footprint "eagle-import:SOT223")
      (libsource (lib "eagle-import") (part "BSP170P"))
    )
    (comp (ref "Q6")
      (value "BC857CSMD")
      (footprint "eagle-import:SOT23-BEC")
      (libsource (lib "eagle-import") (part "BC857SMDC"))
    )
    (comp (ref "R2")
      (value "1k")
      (footprint "eagle-import:R0805")
      (libsource (lib "eagle-import") (part "R-EU_R0805"))
    )
    (comp (ref "R3")
      (value "1k")
      (footprint "eagle-import:R0805")
      (libsource (lib "eagle-import") (part "R-EU_R0805"))
    )
    (comp (ref "R4")
      (value "1k 1%")
      (footprint "eagle-import:R0805")
      (libsource (lib "eagle-import") (part "R-EU_R0805"))
    )
    (comp (ref "R5")
      (value "5k6")
      (footprint "eagle-import:R0805")
      (libsource (lib "eagle-import") (part "R-EU_R0805"))
    )
    (comp (ref "R6")
      (value "200R 1%")
      (footprint "eagle-import:R0805")
      (libsource (lib "eagle-import") (part "R-EU_R0805"))
    )
    (comp (ref "R7")
      (value "1k")
      (footprint "eagle-import:R0805")
      (libsource (lib "eagle-import") (part "R-EU_R0805"))
    )
    (comp (ref "R18")
      (value "1k")
      (footprint "eagle-import:R0805")
      (libsource (lib "eagle-import") (part "R-EU_R0805"))
    )
    (comp (ref "R20")
      (value "18R 1%")
      (footprint "eagle-import:R1206")
      (libsource (lib "eagle-import") (part "R-EU_R1206"))
    )
    (comp (ref "R21")
      (value "0R")
      (footprint "eagle-import:R1206")
      (libsource (lib "eagle-import") (part "R-EU_R1206"))
    )
    (comp (ref "R47")
      (value "20k 1%")
      (footprint "eagle-import:R0805")
      (libsource (lib "eagle-import") (part "R-EU_R0805"))
    )
    (comp (ref "R48")
      (value "180k 1%")
      (footprint "eagle-import:R0805")
      (libsource (lib "eagle-import") (part "R-EU_R0805"))
    )
    (comp (ref "R50")
      (value "100R")
      (footprint "eagle-import:R0805")
      (libsource (lib "eagle-import") (part "R-EU_R0805"))
    )
    (comp (ref "R51")
      (value "100R")
      (footprint "eagle-import:R0805")
      (libsource (lib "eagle-import") (part "R-EU_R0805"))
    )
    (comp (ref "R52")
      (value "0R")
      (footprint "eagle-import:R1206")
      (libsource (lib "eagle-import") (part "R-EU_R1206"))
    )
    (comp (ref "R53")
      (value "2R 1%")
      (footprint "eagle-import:R1206")
      (libsource (lib "eagle-import") (part "R-EU_R1206"))
    )
    (comp (ref "R54")
      (value "1R")
      (footprint "eagle-import:R0805")
      (libsource (lib "eagle-import") (part "R-EU_R0805"))
    )
    (comp (ref "R58")
      (value "1R")
      (footprint "eagle-import:R0805")
      (libsource (lib "eagle-import") (part "R-EU_R0805"))
    )
    (comp (ref "R59")
      (value "1R")
      (footprint "eagle-import:R0805")
      (libsource (lib "eagle-import") (part "R-EU_R0805"))
    )
    (comp (ref "R61")
      (value "0R")
      (footprint "eagle-import:R1206")
      (libsource (lib "eagle-import") (part "R-EU_R1206"))
    )
    (comp (ref "R79")
      (value "680k")
      (footprint "eagle-import:R0805")
      (libsource (lib "eagle-import") (part "R-EU_R0805"))
    )
    (comp (ref "R80")
      (value "20k")
      (footprint "eagle-import:R0805")
      (libsource (lib "eagle-import") (part "R-EU_R0805"))
    )
    (comp (ref "R81")
      (value "20k")
      (footprint "eagle-import:R0805")
      (libsource (lib "eagle-import") (part "R-EU_R0805"))
    )
    (comp (ref "T4")
      (value "BC847C")
      (footprint "eagle-import:SOT23")
      (libsource (lib "eagle-import") (part "BC847"))
    )
    (comp (ref "U4")
      (value "INA186A2")
      (footprint "eagle-import:SC70-6L")
      (libsource (lib "eagle-import") (part "INA186A2"))
    )
    (comp (ref "C17")
      (value "100n")
      (footprint "eagle-import:C0805")
      (libsource (lib "eagle-import") (part "C-EUC0805"))
    )
    (comp (ref "C68")
      (value "100n")
      (footprint "eagle-import:C0805")
      (libsource (lib "eagle-import") (part "C-EUC0805"))
    )
    (comp (ref "D1")
      (value "SM712-02HTG")
      (footprint "eagle-import:SOT23-BEC")
      (libsource (lib "eagle-import") (part "SM712-02HTG"))
    )
    (comp (ref "K2")
      (value "09 03 364 6921")
      (footprint "eagle-import:VG64P")
      (libsource (lib "eagle-import") (part "VG64P"))
    )
    (comp (ref "LED5")
      (value "GREEN")
      (footprint "eagle-import:CHIPLED_1206")
      (libsource (lib "eagle-import") (part "LEDCHIPLED_1206"))
    )
    (comp (ref "LED6")
      (value "RED")
      (footprint "eagle-import:CHIPLED_1206")
      (libsource (lib "eagle-import") (part "LEDCHIPLED_1206"))
    )
    (comp (ref "R13")
      (value "10R")
      (footprint "eagle-import:R0603")
      (libsource (lib "eagle-import") (part "R-EU_R0603"))
    )
    (comp (ref "R14")
      (value "10R")
      (footprint "eagle-import:R0603")
      (libsource (lib "eagle-import") (part "R-EU_R0603"))
    )
    (comp (ref "R15")
      (value "1k")
      (footprint "eagle-import:R1206")
      (libsource (lib "eagle-import") (part "R-EU_R1206"))
    )
    (comp (ref "R16")
      (value "1k")
      (footprint "eagle-import:R1206")
      (libsource (lib "eagle-import") (part "R-EU_R1206"))
    )
    (comp (ref "R17")
      (value "130R")
      (footprint "eagle-import:R1206")
      (libsource (lib "eagle-import") (part "R-EU_R1206"))
    )
    (comp (ref "R30")
      (value "1k5")
      (footprint "eagle-import:R1206")
      (libsource (lib "eagle-import") (part "R-EU_R1206"))
    )
    (comp (ref "R31")
      (value "1k5")
      (footprint "eagle-import:R1206")
      (libsource (lib "eagle-import") (part "R-EU_R1206"))
    )
    (comp (ref "R32")
      (value "10k")
      (footprint "eagle-import:R0603")
      (libsource (lib "eagle-import") (part "R-EU_R0603"))
    )
    (comp (ref "R49")
      (value "0R1")
      (footprint "eagle-import:R1206")
      (libsource (lib "eagle-import") (part "R-EU_R1206"))
    )
    (comp (ref "S1")
      (value "SWS003")
      (footprint "eagle-import:SMS-003")
      (libsource (lib "eagle-import") (part "SWS003"))
    )
    (comp (ref "U30")
      (value "ISO3082")
      (footprint "eagle-import:SO-16DW")
      (libsource (lib "eagle-import") (part "ISO3082"))
    )
    (comp (ref "LED1")
      (value "GREEN")
      (footprint "eagle-import:LED3MM")
      (libsource (lib "eagle-import") (part "LED3MM"))
    )
    (comp (ref "LED2")
      (value "RED")
      (footprint "eagle-import:LED3MM")
      (libsource (lib "eagle-import") (part "LED3MM"))
    )
    (comp (ref "LED7")
      (value "BLUE")
      (footprint "eagle-import:LED3MM")
      (libsource (lib "eagle-import") (part "LED3MM"))
    )
    (comp (ref "LED8")
      (value "YELLOW")
      (footprint "eagle-import:LED3MM")
      (libsource (lib "eagle-import") (part "LED3MM"))
    )
    (comp (ref "LED9")
      (value "GREEN")
      (footprint "eagle-import:LED3MM")
      (libsource (lib "eagle-import") (part "LED3MM"))
    )
    (comp (ref "LED10")
      (value "RED")
      (footprint "eagle-import:LED3MM")
      (libsource (lib "eagle-import") (part "LED3MM"))
    )
    (comp (ref "LED11")
      (value "BLUE")
      (footprint "eagle-import:LED3MM")
      (libsource (lib "eagle-import") (part "LED3MM"))
    )
    (comp (ref "LED12")
      (value "YELLOW")
      (footprint "eagle-import:LED3MM")
      (libsource (lib "eagle-import") (part "LED3MM"))
    )
    (comp (ref "LED13")
      (value "GREEN")
      (footprint "eagle-import:LED3MM")
      (libsource (lib "eagle-import") (part "LED3MM"))
    )
    (comp (ref "LED14")
      (value "RED")
      (footprint "eagle-import:LED3MM")
      (libsource (lib "eagle-import") (part "LED3MM"))
    )
    (comp (ref "LED15")
      (value "BLUE")
      (footprint "eagle-import:LED3MM")
      (libsource (lib "eagle-import") (part "LED3MM"))
    )
    (comp (ref "LED16")
      (value "YELLOW")
      (footprint "eagle-import:LED3MM")
      (libsource (lib "eagle-import") (part "LED3MM"))
    )
    (comp (ref "R63")
      (value "470R")
      (footprint "eagle-import:R1206")
      (libsource (lib "eagle-import") (part "R-EU_R1206"))
    )
    (comp (ref "R64")
      (value "470R")
      (footprint "eagle-import:R1206")
      (libsource (lib "eagle-import") (part "R-EU_R1206"))
    )
    (comp (ref "R65")
      (value "470R")
      (footprint "eagle-import:R1206")
      (libsource (lib "eagle-import") (part "R-EU_R1206"))
    )
    (comp (ref "R66")
      (value "470R")
      (footprint "eagle-import:R1206")
      (libsource (lib "eagle-import") (part "R-EU_R1206"))
    )
    (comp (ref "R67")
      (value "470R")
      (footprint "eagle-import:R1206")
      (libsource (lib "eagle-import") (part "R-EU_R1206"))
    )
    (comp (ref "R68")
      (value "470R")
      (footprint "eagle-import:R1206")
      (libsource (lib "eagle-import") (part "R-EU_R1206"))
    )
    (comp (ref "R69")
      (value "470R")
      (footprint "eagle-import:R1206")
      (libsource (lib "eagle-import") (part "R-EU_R1206"))
    )
    (comp (ref "R70")
      (value "470R")
      (footprint "eagle-import:R1206")
      (libsource (lib "eagle-import") (part "R-EU_R1206"))
    )
    (comp (ref "R71")
      (value "470R")
      (footprint "eagle-import:R1206")
      (libsource (lib "eagle-import") (part "R-EU_R1206"))
    )
    (comp (ref "R72")
      (value "470R")
      (footprint "eagle-import:R1206")
      (libsource (lib "eagle-import") (part "R-EU_R1206"))
    )
    (comp (ref "R73")
      (value "470R")
      (footprint "eagle-import:R1206")
      (libsource (lib "eagle-import") (part "R-EU_R1206"))
    )
    (comp (ref "R74")
      (value "470R")
      (footprint "eagle-import:R1206")
      (libsource (lib "eagle-import") (part "R-EU_R1206"))
    )
  )
  (nets
    (net (code "1") (name "+3V3") (class "Default")
      (node (ref "C1") (pin "1") (pinfunction "1_1") (pintype "passive"))
      (node (ref "C10") (pin "1") (pinfunction "1_1") (pintype "passive"))
      (node (ref "C2") (pin "1") (pinfunction "1_1") (pintype "passive"))
      (node (ref "C27") (pin "+") (pinfunction "+_+") (pintype "passive"))
      (node (ref "C28") (pin "1") (pinfunction "1_1") (pintype "passive"))
      (node (ref "C3") (pin "1") (pinfunction "1_1") (pintype "passive"))
      (node (ref "C5") (pin "1") (pinfunction "1_1") (pintype "passive"))
      (node (ref "C7") (pin "1") (pinfunction "1_1") (pintype "passive"))
      (node (ref "C8") (pin "1") (pinfunction "1_1") (pintype "passive"))
      (node (ref "C9") (pin "1") (pinfunction "1_1") (pintype "passive"))
      (node (ref "K1") (pin "1") (pinfunction "VCC_1") (pintype "bidirectional"))
      (node (ref "L1") (pin "2") (pinfunction "2_2") (pintype "passive"))
      (node (ref "LED1") (pin "A") (pinfunction "A_A") (pintype "passive"))
      (node (ref "LED10") (pin "A") (pinfunction "A_A") (pintype "passive"))
      (node (ref "LED11") (pin "A") (pinfunction "A_A") (pintype "passive"))
      (node (ref "LED12") (pin "A") (pinfunction "A_A") (pintype "passive"))
      (node (ref "LED13") (pin "A") (pinfunction "A_A") (pintype "passive"))
      (node (ref "LED14") (pin "A") (pinfunction "A_A") (pintype "passive"))
      (node (ref "LED15") (pin "A") (pinfunction "A_A") (pintype "passive"))
      (node (ref "LED16") (pin "A") (pinfunction "A_A") (pintype "passive"))
      (node (ref "LED2") (pin "A") (pinfunction "A_A") (pintype "passive"))
      (node (ref "LED5") (pin "A") (pinfunction "A_A") (pintype "passive"))
      (node (ref "LED6") (pin "A") (pinfunction "A_A") (pintype "passive"))
      (node (ref "LED7") (pin "A") (pinfunction "A_A") (pintype "passive"))
      (node (ref "LED8") (pin "A") (pinfunction "A_A") (pintype "passive"))
      (node (ref "LED9") (pin "A") (pinfunction "A_A") (pintype "passive"))
      (node (ref "R12") (pin "2") (pinfunction "2_2") (pintype "passive"))
      (node (ref "R27") (pin "1") (pinfunction "1_1") (pintype "passive"))
      (node (ref "R46") (pin "1") (pinfunction "1_1") (pintype "passive"))
      (node (ref "R49") (pin "2") (pinfunction "2_2") (pintype "passive"))
      (node (ref "R54") (pin "2") (pinfunction "2_2") (pintype "passive"))
      (node (ref "R55") (pin "2") (pinfunction "2_2") (pintype "passive"))
      (node (ref "R56") (pin "2") (pinfunction "2_2") (pintype "passive"))
      (node (ref "R60") (pin "2") (pinfunction "2_2") (pintype "passive"))
      (node (ref "R77") (pin "1") (pinfunction "1_1") (pintype "passive"))
      (node (ref "R80") (pin "1") (pinfunction "1_1") (pintype "passive"))
      (node (ref "R9") (pin "1") (pinfunction "1_1") (pintype "passive"))
      (node (ref "U1") (pin "100") (pinfunction "VDD_4_100") (pintype "power_in"))
      (node (ref "U1") (pin "28") (pinfunction "VDD_1_28") (pintype "power_in"))
      (node (ref "U1") (pin "50") (pinfunction "VDD_2_50") (pintype "power_in"))
      (node (ref "U1") (pin "73") (pinfunction "VDD_3_73") (pintype "power_in"))
      (node (ref "U1") (pin "75") (pinfunction "VDD_USB_75") (pintype "power_in"))
      (node (ref "U3") (pin "3") (pinfunction "+VOUT_3") (pintype "bidirectional"))
    )
    (net (code "2") (name "+24V") (class "Default")
      (node (ref "C22") (pin "+") (pinfunction "+_+") (pintype "passive"))
      (node (ref "C23") (pin "1") (pinfunction "1_1") (pintype "passive"))
      (node (ref "C29") (pin "1") (pinfunction "1_1") (pintype "passive"))
      (node (ref "C40") (pin "1") (pinfunction "1_1") (pintype "passive"))
      (node (ref "IC2") (pin "7") (pinfunction "V+_7") (pintype "power_in"))
      (node (ref "L3") (pin "1") (pinfunction "1_1") (pintype "passive"))
      (node (ref "R1") (pin "2") (pinfunction "2_2") (pintype "passive"))
      (node (ref "R57") (pin "2") (pinfunction "2_2") (pintype "passive"))
      (node (ref "R59") (pin "2") (pinfunction "2_2") (pintype "passive"))
      (node (ref "R61") (pin "2") (pinfunction "2_2") (pintype "passive"))
    )
    (net (code "3") (name "+24V_IN") (class "Default")
      (node (ref "K2") (pin "A30") (pinfunction "A30_A30") (pintype "passive"))
      (node (ref "K2") (pin "A31") (pinfunction "A31_A31") (pintype "passive"))
      (node (ref "K2") (pin "A32") (pinfunction "A32_A32") (pintype "passive"))
      (node (ref "K2") (pin "C30") (pinfunction "C30_C30") (pintype "passive"))
      (node (ref "K2") (pin "C31") (pinfunction "C31_C31") (pintype "passive"))
      (node (ref "K2") (pin "C32") (pinfunction "C32_C32") (pintype "passive"))
      (node (ref "L2") (pin "1") (pinfunction "1_1") (pintype "passive"))
    )
    (net (code "4") (name "ADC_CURRENT") (class "Default")
      (node (ref "C45") (pin "1") (pinfunction "1_1") (pintype "passive"))
      (node (ref "R34") (pin "2") (pinfunction "2_2") (pintype "passive"))
      (node (ref "U1") (pin "25") (pinfunction "PA2_25") (pintype "bidirectional"))
    )
    (net (code "5") (name "ADC_CURRENT_MONITOR") (class "Default")
      (node (ref "C46") (pin "1") (pinfunction "1_1") (pintype "passive"))
      (node (ref "R43") (pin "2") (pinfunction "2_2") (pintype "passive"))
      (node (ref "U1") (pin "16") (pinfunction "PC1_16") (pintype "bidirectional"))
    )
    (net (code "6") (name "ADC_CURRENT_THERMOSTAT") (class "Default")
      (node (ref "C44") (pin "1") (pinfunction "1_1") (pintype "passive"))
      (node (ref "R52") (pin "2") (pinfunction "2_2") (pintype "passive"))
      (node (ref "U1") (pin "35") (pinfunction "PB0_35") (pintype "bidirectional"))
    )
    (net (code "7") (name "ADC_VOLTAGE") (class "Default")
      (node (ref "C25") (pin "1") (pinfunction "1_1") (pintype "passive"))
      (node (ref "R35") (pin "2") (pinfunction "2_2") (pintype "passive"))
      (node (ref "R36") (pin "1") (pinfunction "1_1") (pintype "passive"))
      (node (ref "U1") (pin "26") (pinfunction "PA3_26") (pintype "bidirectional"))
    )
    (net (code "8") (name "ADC_VOLTAGE_MONITOR") (class "Default")
      (node (ref "R39") (pin "2") (pinfunction "2_2") (pintype "passive"))
      (node (ref "U1") (pin "15") (pinfunction "PC0_15") (pintype "bidirectional"))
    )
    (net (code "9") (name "ADC_VOLTAGE_THERMOSTAT") (class "Default")
      (node (ref "C33") (pin "1") (pinfunction "1_1") (pintype "passive"))
      (node (ref "R47") (pin "2") (pinfunction "2_2") (pintype "passive"))
      (node (ref "R48") (pin "1") (pinfunction "1_1") (pintype "passive"))
      (node (ref "U1") (pin "36") (pinfunction "PB1_36") (pintype "bidirectional"))
    )
    (net (code "10") (name "ADDR1_HEX") (class "Default")
      (node (ref "U1") (pin "61") (pinfunction "PD14_61") (pintype "bidirectional"))
      (node (ref "U2") (pin "1") (pinfunction "1_1") (pintype "bidirectional"))
    )
    (net (code "11") (name "ADDR2_HEX") (class "Default")
      (node (ref "U1") (pin "59") (pinfunction "PD12_59") (pintype "bidirectional"))
      (node (ref "U2") (pin "2") (pinfunction "2_2") (pintype "bidirectional"))
    )
    (net (code "12") (name "ADDR4_HEX") (class "Default")
      (node (ref "U1") (pin "62") (pinfunction "PD15_62") (pintype "bidirectional"))
      (node (ref "U2") (pin "4") (pinfunction "4_4") (pintype "bidirectional"))
    )
    (net (code "13") (name "ADDR8_HEX") (class "Default")
      (node (ref "U1") (pin "60") (pinfunction "PD13_60") (pintype "bidirectional"))
      (node (ref "U2") (pin "8") (pinfunction "8_8") (pintype "bidirectional"))
    )
    (net (code "14") (name "AUX_1") (class "Default")
      (node (ref "K2") (pin "A2") (pinfunction "A2_A2") (pintype "passive"))
    )
    (net (code "15") (name "AUX_2") (class "Default")
      (node (ref "K2") (pin "C2") (pinfunction "C2_C2") (pintype "passive"))
    )
    (net (code "16") (name "AUX_3") (class "Default")
      (node (ref "K2") (pin "A4") (pinfunction "A4_A4") (pintype "passive"))
    )
    (net (code "17") (name "AUX_4") (class "Default")
      (node (ref "K2") (pin "C4") (pinfunction "C4_C4") (pintype "passive"))
    )
    (net (code "18") (name "AUX_5") (class "Default")
      (node (ref "K2") (pin "A5") (pinfunction "A5_A5") (pintype "passive"))
    )
    (net (code "19") (name "AUX_6") (class "Default")
      (node (ref "K2") (pin "C5") (pinfunction "C5_C5") (pintype "passive"))
    )
    (net (code "20") (name "AUX_7") (class "Default")
      (node (ref "K2") (pin "A6") (pinfunction "A6_A6") (pintype "passive"))
    )
    (net (code "21") (name "AUX_8") (class "Default")
      (node (ref "K2") (pin "C6") (pinfunction "C6_C6") (pintype "passive"))
    )
    (net (code "22") (name "AUX_9") (class "Default")
      (node (ref "K2") (pin "A7") (pinfunction "A7_A7") (pintype "passive"))
    )
    (net (code "23") (name "AUX_10") (class "Default")
      (node (ref "K2") (pin "C7") (pinfunction "C7_C7") (pintype "passive"))
    )
    (net (code "24") (name "AUX_11") (class "Default")
      (node (ref "K2") (pin "A8") (pinfunction "A8_A8") (pintype "passive"))
    )
    (net (code "25") (name "AUX_12") (class "Default")
      (node (ref "K2") (pin "C8") (pinfunction "C8_C8") (pintype "passive"))
    )
    (net (code "26") (name "AUX_13") (class "Default")
      (node (ref "K2") (pin "A9") (pinfunction "A9_A9") (pintype "passive"))
    )
    (net (code "27") (name "AUX_14") (class "Default")
      (node (ref "K2") (pin "C9") (pinfunction "C9_C9") (pintype "passive"))
    )
    (net (code "28") (name "AUX_15") (class "Default")
      (node (ref "K2") (pin "A10") (pinfunction "A10_A10") (pintype "passive"))
    )
    (net (code "29") (name "AUX_16") (class "Default")
      (node (ref "K2") (pin "C10") (pinfunction "C10_C10") (pintype "passive"))
    )
    (net (code "30") (name "AUX_17") (class "Default")
      (node (ref "K2") (pin "A11") (pinfunction "A11_A11") (pintype "passive"))
    )
    (net (code "31") (name "AUX_18") (class "Default")
      (node (ref "K2") (pin "C11") (pinfunction "C11_C11") (pintype "passive"))
    )
    (net (code "32") (name "AUX_19") (class "Default")
      (node (ref "K2") (pin "A12") (pinfunction "A12_A12") (pintype "passive"))
    )
    (net (code "33") (name "AUX_20") (class "Default")
      (node (ref "K2") (pin "C12") (pinfunction "C12_C12") (pintype "passive"))
    )
    (net (code "34") (name "AUX_21") (class "Default")
      (node (ref "K2") (pin "A13") (pinfunction "A13_A13") (pintype "passive"))
    )
    (net (code "35") (name "AUX_22") (class "Default")
      (node (ref "K2") (pin "C13") (pinfunction "C13_C13") (pintype "passive"))
    )
    (net (code "36") (name "AUX_23") (class "Default")
      (node (ref "K2") (pin "A14") (pinfunction "A14_A14") (pintype "passive"))
    )
    (net (code "37") (name "AUX_24") (class "Default")
      (node (ref "K2") (pin "C14") (pinfunction "C14_C14") (pintype "passive"))
    )
    (net (code "38") (name "AUX_25") (class "Default")
      (node (ref "K2") (pin "A15") (pinfunction "A15_A15") (pintype "passive"))
    )
    (net (code "39") (name "AUX_26") (class "Default")
      (node (ref "K2") (pin "C15") (pinfunction "C15_C15") (pintype "passive"))
    )
    (net (code "40") (name "AUX_27") (class "Default")
      (node (ref "K2") (pin "A16") (pinfunction "A16_A16") (pintype "passive"))
    )
    (net (code "41") (name "AUX_28") (class "Default")
      (node (ref "K2") (pin "C16") (pinfunction "C16_C16") (pintype "passive"))
    )
    (net (code "42") (name "AUX_29") (class "Default")
      (node (ref "K2") (pin "A17") (pinfunction "A17_A17") (pintype "passive"))
    )
    (net (code "43") (name "AUX_30") (class "Default")
      (node (ref "K2") (pin "C17") (pinfunction "C17_C17") (pintype "passive"))
    )
    (net (code "44") (name "AUX_31") (class "Default")
      (node (ref "K2") (pin "A18") (pinfunction "A18_A18") (pintype "passive"))
    )
    (net (code "45") (name "AUX_32") (class "Default")
      (node (ref "K2") (pin "C18") (pinfunction "C18_C18") (pintype "passive"))
    )
    (net (code "46") (name "AUX_33") (class "Default")
      (node (ref "K2") (pin "A19") (pinfunction "A19_A19") (pintype "passive"))
    )
    (net (code "47") (name "AUX_34") (class "Default")
      (node (ref "K2") (pin "C19") (pinfunction "C19_C19") (pintype "passive"))
    )
    (net (code "48") (name "AUX_35") (class "Default")
      (node (ref "K2") (pin "A20") (pinfunction "A20_A20") (pintype "passive"))
    )
    (net (code "49") (name "AUX_36") (class "Default")
      (node (ref "K2") (pin "C20") (pinfunction "C20_C20") (pintype "passive"))
    )
    (net (code "50") (name "AUX_37") (class "Default")
      (node (ref "K2") (pin "A21") (pinfunction "A21_A21") (pintype "passive"))
    )
    (net (code "51") (name "AUX_38") (class "Default")
      (node (ref "K2") (pin "C21") (pinfunction "C21_C21") (pintype "passive"))
    )
    (net (code "52") (name "AUX_39") (class "Default")
      (node (ref "K2") (pin "A22") (pinfunction "A22_A22") (pintype "passive"))
    )
    (net (code "53") (name "AUX_40") (class "Default")
      (node (ref "K2") (pin "C22") (pinfunction "C22_C22") (pintype "passive"))
    )
    (net (code "54") (name "AUX_41") (class "Default")
      (node (ref "K2") (pin "A23") (pinfunction "A23_A23") (pintype "passive"))
    )
    (net (code "55") (name "AUX_42") (class "Default")
      (node (ref "K2") (pin "C23") (pinfunction "C23_C23") (pintype "passive"))
    )
    (net (code "56") (name "AUX_43") (class "Default")
      (node (ref "K2") (pin "A24") (pinfunction "A24_A24") (pintype "passive"))
    )
    (net (code "57") (name "AUX_44") (class "Default")
      (node (ref "K2") (pin "C24") (pinfunction "C24_C24") (pintype "passive"))
    )
    (net (code "58") (name "AUX_45") (class "Default")
      (node (ref "K2") (pin "A25") (pinfunction "A25_A25") (pintype "passive"))
    )
    (net (code "59") (name "AUX_46") (class "Default")
      (node (ref "K2") (pin "C25") (pinfunction "C25_C25") (pintype "passive"))
    )
    (net (code "60") (name "AUX_47") (class "Default")
      (node (ref "K2") (pin "A26") (pinfunction "A26_A26") (pintype "passive"))
    )
    (net (code "61") (name "AUX_48") (class "Default")
      (node (ref "K2") (pin "C26") (pinfunction "C26_C26") (pintype "passive"))
    )
    (net (code "62") (name "AUX_MCU4") (class "Default")
      (node (ref "U1") (pin "39") (pinfunction "PE8_39") (pintype "bidirectional"))
    )
    (net (code "63") (name "AUX_MCU5") (class "Default")
      (node (ref "U1") (pin "40") (pinfunction "PE9_40") (pintype "bidirectional"))
    )
    (net (code "64") (name "DAC_CURRENT_THERMOSTAT") (class "Default")
      (node (ref "R21") (pin "1") (pinfunction "1_1") (pintype "passive"))
      (node (ref "U1") (pin "30") (pinfunction "PA5_30") (pintype "bidirectional"))
    )
    (net (code "65") (name "DAC_VOLTAGE") (class "Default")
      (node (ref "R24") (pin "1") (pinfunction "1_1") (pintype "passive"))
      (node (ref "U1") (pin "29") (pinfunction "PA4_29") (pintype "bidirectional"))
    )
    (net (code "66") (name "GND") (class "Default")
      (node (ref "C1") (pin "2") (pinfunction "2_2") (pintype "passive"))
      (node (ref "C10") (pin "2") (pinfunction "2_2") (pintype "passive"))
      (node (ref "C11") (pin "2") (pinfunction "2_2") (pintype "passive"))
      (node (ref "C12") (pin "2") (pinfunction "2_2") (pintype "passive"))
      (node (ref "C13") (pin "2") (pinfunction "2_2") (pintype "passive"))
      (node (ref "C14") (pin "2") (pinfunction "2_2") (pintype "passive"))
      (node (ref "C15") (pin "2") (pinfunction "2_2") (pintype "passive"))
      (node (ref "C16") (pin "2") (pinfunction "2_2") (pintype "passive"))
      (node (ref "C17") (pin "2") (pinfunction "2_2") (pintype "passive"))
      (node (ref "C2") (pin "2") (pinfunction "2_2") (pintype "passive"))
      (node (ref "C22") (pin "-") (pinfunction "-_-") (pintype "passive"))
      (node (ref "C23") (pin "2") (pinfunction "2_2") (pintype "passive"))
      (node (ref "C25") (pin "2") (pinfunction "2_2") (pintype "passive"))
      (node (ref "C27") (pin "-") (pinfunction "-_-") (pintype "passive"))
      (node (ref "C28") (pin "2") (pinfunction "2_2") (pintype "passive"))
      (node (ref "C29") (pin "2") (pinfunction "2_2") (pintype "passive"))
      (node (ref "C3") (pin "2") (pinfunction "2_2") (pintype "passive"))
      (node (ref "C30") (pin "2") (pinfunction "2_2") (pintype "passive"))
      (node (ref "C31") (pin "2") (pinfunction "2_2") (pintype "passive"))
      (node (ref "C32") (pin "1") (pinfunction "1_1") (pintype "passive"))
      (node (ref "C33") (pin "2") (pinfunction "2_2") (pintype "passive"))
      (node (ref "C35") (pin "2") (pinfunction "2_2") (pintype "passive"))
      (node (ref "C36") (pin "2") (pinfunction "2_2") (pintype "passive"))
      (node (ref "C37") (pin "2") (pinfunction "2_2") (pintype "passive"))
      (node (ref "C38") (pin "1") (pinfunction "1_1") (pintype "passive"))
      (node (ref "C39") (pin "2") (pinfunction "2_2") (pintype "passive"))
      (node (ref "C41") (pin "2") (pinfunction "2_2") (pintype "passive"))
      (node (ref "C42") (pin "2") (pinfunction "2_2") (pintype "passive"))
      (node (ref "C43") (pin "1") (pinfunction "1_1") (pintype "passive"))
      (node (ref "C44") (pin "2") (pinfunction "2_2") (pintype "passive"))
      (node (ref "C45") (pin "2") (pinfunction "2_2") (pintype "passive"))
      (node (ref "C46") (pin "2") (pinfunction "2_2") (pintype "passive"))
      (node (ref "C47") (pin "2") (pinfunction "2_2") (pintype "passive"))
      (node (ref "C48") (pin "2") (pinfunction "2_2") (pintype "passive"))
      (node (ref "C49") (pin "1") (pinfunction "1_1") (pintype "passive"))
      (node (ref "C5") (pin "2") (pinfunction "2_2") (pintype "passive"))
      (node (ref "C51") (pin "2") (pinfunction "2_2") (pintype "passive"))
      (node (ref "C52") (pin "2") (pinfunction "2_2") (pintype "passive"))
      (node (ref "C53") (pin "1") (pinfunction "1_1") (pintype "passive"))
      (node (ref "C7") (pin "2") (pinfunction "2_2") (pintype "passive"))
      (node (ref "C8") (pin "2") (pinfunction "2_2") (pintype "passive"))
      (node (ref "C9") (pin "2") (pinfunction "2_2") (pintype "passive"))
      (node (ref "D5") (pin "A") (pinfunction "A_A") (pintype "passive"))
      (node (ref "D6") (pin "A") (pinfunction "A_A") (pintype "passive"))
      (node (ref "D7") (pin "A") (pinfunction "A_A") (pintype "passive"))
      (node (ref "D8") (pin "A") (pinfunction "A_A") (pintype "passive"))
      (node (ref "IC1") (pin "4") (pinfunction "V-_4") (pintype "power_in"))
      (node (ref "IC3") (pin "4") (pinfunction "V-_4") (pintype "power_in"))
      (node (ref "IC4") (pin "4") (pinfunction "V-_4") (pintype "power_in"))
      (node (ref "IC5") (pin "3") (pinfunction "GND_3") (pintype "passive"))
      (node (ref "K1") (pin "3") (pinfunction "GND_3") (pintype "bidirectional"))
      (node (ref "K1") (pin "5") (pinfunction "GND_5") (pintype "bidirectional"))
      (node (ref "K1") (pin "9") (pinfunction "GNDDTCT_9") (pintype "bidirectional"))
      (node (ref "PL1") (pin "1") (pinfunction "S_1") (pintype "passive"))
      (node (ref "PL1") (pin "2") (pinfunction "S_2") (pintype "passive"))
      (node (ref "PL2") (pin "1") (pinfunction "S_1") (pintype "passive"))
      (node (ref "PL2") (pin "2") (pinfunction "S_2") (pintype "passive"))
      (node (ref "PL3") (pin "1") (pinfunction "S_1") (pintype "passive"))
      (node (ref "PL3") (pin "2") (pinfunction "S_2") (pintype "passive"))
      (node (ref "Q4") (pin "C") (pinfunction "C_C") (pintype "passive"))
      (node (ref "Q5") (pin "C") (pinfunction "C_C") (pintype "passive"))
      (node (ref "Q6") (pin "C") (pinfunction "C_C") (pintype "passive"))
      (node (ref "R11") (pin "1") (pinfunction "1_1") (pintype "passive"))
      (node (ref "R22") (pin "1") (pinfunction "1_1") (pintype "passive"))
      (node (ref "R23") (pin "1") (pinfunction "1_1") (pintype "passive"))
      (node (ref "R32") (pin "1") (pinfunction "1_1") (pintype "passive"))
      (node (ref "R35") (pin "1") (pinfunction "1_1") (pintype "passive"))
      (node (ref "R37") (pin "1") (pinfunction "1_1") (pintype "passive"))
      (node (ref "R4") (pin "1") (pinfunction "1_1") (pintype "passive"))
      (node (ref "R44") (pin "1") (pinfunction "1_1") (pintype "passive"))
      (node (ref "R47") (pin "1") (pinfunction "1_1") (pintype "passive"))
      (node (ref "R58") (pin "1") (pinfunction "1_1") (pintype "passive"))
      (node (ref "SW1") (pin "3") (pinfunction "2_3") (pintype "passive"))
      (node (ref "T1") (pin "1") (pinfunction "B_1") (pintype "passive"))
      (node (ref "T3") (pin "1") (pinfunction "B_1") (pintype "passive"))
      (node (ref "T4") (pin "1") (pinfunction "B_1") (pintype "passive"))
      (node (ref "U1") (pin "19") (pinfunction "VSSA_19") (pintype "power_in"))
      (node (ref "U1") (pin "20") (pinfunction "VREF_20") (pintype "power_in"))
      (node (ref "U1") (pin "27") (pinfunction "VSS_1_27") (pintype "power_in"))
      (node (ref "U1") (pin "49") (pinfunction "VSS_2_49") (pintype "power_in"))
      (node (ref "U1") (pin "74") (pinfunction "VSS_3_74") (pintype "power_in"))
      (node (ref "U1") (pin "99") (pinfunction "VSS_4_99") (pintype "power_in"))
      (node (ref "U2") (pin "C1") (pinfunction "COM1_C1") (pintype "bidirectional"))
      (node (ref "U2") (pin "C2") (pinfunction "COM2_C2") (pintype "bidirectional"))
      (node (ref "U3") (pin "2") (pinfunction "GND_2") (pintype "bidirectional"))
      (node (ref "U30") (pin "2") (pinfunction "GND1_2") (pintype "input"))
      (node (ref "U30") (pin "7") (pinfunction "GND1_7") (pintype "input"))
      (node (ref "U30") (pin "8") (pinfunction "GND1_8") (pintype "input"))
      (node (ref "U4") (pin "1") (pinfunction "REF_1") (pintype "bidirectional"))
      (node (ref "U4") (pin "2") (pinfunction "GND_2") (pintype "bidirectional"))
      (node (ref "U5") (pin "1") (pinfunction "REF_1") (pintype "bidirectional"))
      (node (ref "U5") (pin "2") (pinfunction "GND_2") (pintype "bidirectional"))
      (node (ref "U6") (pin "2") (pinfunction "GND_2") (pintype "bidirectional"))
      (node (ref "U7") (pin "VOUT-") (pinfunction "-VOUT_VOUT-") (pintype "bidirectional"))
      (node (ref "ZD1") (pin "2") (pinfunction "A_2") (pintype "passive"))
    )
    (net (code "67") (name "GND1") (class "Default")
      (node (ref "C18") (pin "2") (pinfunction "2_2") (pintype "passive"))
      (node (ref "C19") (pin "2") (pinfunction "2_2") (pintype "passive"))
      (node (ref "C20") (pin "2") (pinfunction "2_2") (pintype "passive"))
      (node (ref "C21") (pin "-") (pinfunction "-_-") (pintype "passive"))
      (node (ref "C65") (pin "2") (pinfunction "2_2") (pintype "passive"))
      (node (ref "C66") (pin "-") (pinfunction "-_-") (pintype "passive"))
      (node (ref "C68") (pin "2") (pinfunction "2_2") (pintype "passive"))
      (node (ref "D1") (pin "C") (pinfunction "E_C") (pintype "passive"))
      (node (ref "D2") (pin "A") (pinfunction "A_A") (pintype "passive"))
      (node (ref "K2") (pin "A27") (pinfunction "A27_A27") (pintype "passive"))
      (node (ref "K2") (pin "A28") (pinfunction "A28_A28") (pintype "passive"))
      (node (ref "K2") (pin "A29") (pinfunction "A29_A29") (pintype "passive"))
      (node (ref "K2") (pin "C27") (pinfunction "C27_C27") (pintype "passive"))
      (node (ref "K2") (pin "C28") (pinfunction "C28_C28") (pintype "passive"))
      (node (ref "K2") (pin "C29") (pinfunction "C29_C29") (pintype "passive"))
      (node (ref "R10") (pin "1") (pinfunction "1_1") (pintype "passive"))
      (node (ref "R16") (pin "1") (pinfunction "1_1") (pintype "passive"))
      (node (ref "U30") (pin "10") (pinfunction "GND2_10") (pintype "input"))
      (node (ref "U30") (pin "15") (pinfunction "GND2_15") (pintype "input"))
      (node (ref "U30") (pin "9") (pinfunction "GND2_9") (pintype "input"))
      (node (ref "U31") (pin "2") (pinfunction "GND_2") (pintype "bidirectional"))
      (node (ref "U7") (pin "VIN-") (pinfunction "-VIN_VIN-") (pintype "bidirectional"))
    )
    (net (code "68") (name "LED1") (class "Default")
      (node (ref "R63") (pin "2") (pinfunction "2_2") (pintype "passive"))
      (node (ref "U1") (pin "88") (pinfunction "PD7_88") (pintype "bidirectional"))
    )
    (net (code "69") (name "LED2") (class "Default")
      (node (ref "R64") (pin "2") (pinfunction "2_2") (pintype "passive"))
      (node (ref "U1") (pin "89") (pinfunction "PB3_89") (pintype "bidirectional"))
    )
    (net (code "70") (name "LED3") (class "Default")
      (node (ref "R65") (pin "2") (pinfunction "2_2") (pintype "passive"))
      (node (ref "U1") (pin "90") (pinfunction "PB4_90") (pintype "bidirectional"))
    )
    (net (code "71") (name "LED4") (class "Default")
      (node (ref "R66") (pin "2") (pinfunction "2_2") (pintype "passive"))
      (node (ref "U1") (pin "91") (pinfunction "PB5_91") (pintype "bidirectional"))
    )
    (net (code "72") (name "LED5") (class "Default")
      (node (ref "R67") (pin "2") (pinfunction "2_2") (pintype "passive"))
      (node (ref "U1") (pin "1") (pinfunction "PE2_1") (pintype "bidirectional"))
    )
    (net (code "73") (name "LED6") (class "Default")
      (node (ref "R68") (pin "2") (pinfunction "2_2") (pintype "passive"))
      (node (ref "U1") (pin "2") (pinfunction "PE3_2") (pintype "bidirectional"))
    )
    (net (code "74") (name "LED7") (class "Default")
      (node (ref "R69") (pin "2") (pinfunction "2_2") (pintype "passive"))
      (node (ref "U1") (pin "3") (pinfunction "PE4_3") (pintype "bidirectional"))
    )
    (net (code "75") (name "LED8") (class "Default")
      (node (ref "R70") (pin "2") (pinfunction "2_2") (pintype "passive"))
      (node (ref "U1") (pin "4") (pinfunction "PE5_4") (pintype "bidirectional"))
    )
    (net (code "76") (name "LED9") (class "Default")
      (node (ref "R71") (pin "2") (pinfunction "2_2") (pintype "passive"))
      (node (ref "U1") (pin "31") (pinfunction "PA6_31") (pintype "bidirectional"))
    )
    (net (code "77") (name "LED10") (class "Default")
      (node (ref "R72") (pin "2") (pinfunction "2_2") (pintype "passive"))
      (node (ref "U1") (pin "32") (pinfunction "PA7_32") (pintype "bidirectional"))
    )
    (net (code "78") (name "LED11") (class "Default")
      (node (ref "R73") (pin "2") (pinfunction "2_2") (pintype "passive"))
      (node (ref "U1") (pin "33") (pinfunction "PC4_33") (pintype "bidirectional"))
    )
    (net (code "79") (name "LED12") (class "Default")
      (node (ref "R74") (pin "2") (pinfunction "2_2") (pintype "passive"))
      (node (ref "U1") (pin "34") (pinfunction "PC5_34") (pintype "bidirectional"))
    )
    (net (code "80") (name "MODBUS_A") (class "Default")
      (node (ref "D1") (pin "E") (pinfunction "2_E") (pintype "passive"))
      (node (ref "K2") (pin "A3") (pinfunction "A3_A3") (pintype "passive"))
      (node (ref "K2") (pin "C3") (pinfunction "C3_C3") (pintype "passive"))
      (node (ref "R13") (pin "1") (pinfunction "1_1") (pintype "passive"))
      (node (ref "R17") (pin "1") (pinfunction "1_1") (pintype "passive"))
      (node (ref "S1") (pin "6") (pinfunction "6_6") (pintype "passive"))
    )
    (net (code "81") (name "MODBUS_B") (class "Default")
      (node (ref "D1") (pin "B") (pinfunction "1_B") (pintype "passive"))
      (node (ref "K2") (pin "A1") (pinfunction "A1_A1") (pintype "passive"))
      (node (ref "K2") (pin "C1") (pinfunction "C1_C1") (pintype "passive"))
      (node (ref "R14") (pin "1") (pinfunction "1_1") (pintype "passive"))
      (node (ref "S1") (pin "2") (pinfunction "2_2") (pintype "passive"))
      (node (ref "S1") (pin "4") (pinfunction "4_4") (pintype "passive"))
    )
    (net (code "82") (name "NRST") (class "Default")
      (node (ref "C16") (pin "1") (pinfunction "1_1") (pintype "passive"))
      (node (ref "K1") (pin "10") (pinfunction "~{RESET}_10") (pintype "bidirectional"))
      (node (ref "R12") (pin "1") (pinfunction "1_1") (pintype "passive"))
      (node (ref "SW1") (pin "1") (pinfunction "1_1") (pintype "passive"))
      (node (ref "U1") (pin "14") (pinfunction "NRST_14") (pintype "input"))
    )
    (net (code "83") (name "Net-(C31-Pad1)") (class "Default")
      (node (ref "C31") (pin "1") (pinfunction "1_1") (pintype "passive"))
      (node (ref "R39") (pin "1") (pinfunction "1_1") (pintype "passive"))
      (node (ref "R44") (pin "2") (pinfunction "2_2") (pintype "passive"))
      (node (ref "R45") (pin "1") (pinfunction "1_1") (pintype "passive"))
    )
    (net (code "84") (name "Net-(D4-A)") (class "Default")
      (node (ref "D4") (pin "1") (pinfunction "A_1") (pintype "passive"))
      (node (ref "Q2") (pin "2") (pinfunction "D_2") (pintype "passive"))
      (node (ref "Q2") (pin "4") (pinfunction "D_4") (pintype "passive"))
    )
    (net (code "85") (name "Net-(D11-A)") (class "Default")
      (node (ref "D11") (pin "1") (pinfunction "A_1") (pintype "passive"))
      (node (ref "T1") (pin "2") (pinfunction "E_2") (pintype "passive"))
    )
    (net (code "86") (name "Net-(D11-C)") (class "Default")
      (node (ref "D11") (pin "3") (pinfunction "C_3") (pintype "passive"))
      (node (ref "R75") (pin "1") (pinfunction "1_1") (pintype "passive"))
    )
    (net (code "87") (name "Net-(D12-A)") (class "Default")
      (node (ref "D12") (pin "1") (pinfunction "A_1") (pintype "passive"))
      (node (ref "T3") (pin "2") (pinfunction "E_2") (pintype "passive"))
    )
    (net (code "88") (name "Net-(D12-C)") (class "Default")
      (node (ref "D12") (pin "3") (pinfunction "C_3") (pintype "passive"))
      (node (ref "R78") (pin "1") (pinfunction "1_1") (pintype "passive"))
    )
    (net (code "89") (name "Net-(D13-A)") (class "Default")
      (node (ref "D13") (pin "1") (pinfunction "A_1") (pintype "passive"))
      (node (ref "T4") (pin "2") (pinfunction "E_2") (pintype "passive"))
    )
    (net (code "90") (name "Net-(D13-C)") (class "Default")
      (node (ref "D13") (pin "3") (pinfunction "C_3") (pintype "passive"))
      (node (ref "R81") (pin "1") (pinfunction "1_1") (pintype "passive"))
    )
    (net (code "91") (name "Net-(D14-C)") (class "Default")
      (node (ref "D14") (pin "3") (pinfunction "C_3") (pintype "passive"))
      (node (ref "R28") (pin "2") (pinfunction "2_2") (pintype "passive"))
      (node (ref "R29") (pin "1") (pinfunction "1_1") (pintype "passive"))
    )
    (net (code "92") (name "Net-(IC1-+IN)") (class "Default")
      (node (ref "C43") (pin "2") (pinfunction "2_2") (pintype "passive"))
      (node (ref "IC1") (pin "3") (pinfunction "+IN_3") (pintype "input"))
      (node (ref "R21") (pin "2") (pinfunction "2_2") (pintype "passive"))
    )
    (net (code "93") (name "Net-(IC1--IN)") (class "Default")
      (node (ref "C4") (pin "2") (pinfunction "2_2") (pintype "passive"))
      (node (ref "IC1") (pin "2") (pinfunction "-IN_2") (pintype "input"))
      (node (ref "R3") (pin "1") (pinfunction "1_1") (pintype "passive"))
    )
    (net (code "94") (name "Net-(IC1-OUT)") (class "Default")
      (node (ref "C4") (pin "1") (pinfunction "1_1") (pintype "passive"))
      (node (ref "IC1") (pin "6") (pinfunction "OUT_6") (pintype "output"))
      (node (ref "R2") (pin "1") (pinfunction "1_1") (pintype "passive"))
    )
    (net (code "95") (name "Net-(IC1-V+)") (class "Default")
      (node (ref "C41") (pin "1") (pinfunction "1_1") (pintype "passive"))
      (node (ref "IC1") (pin "7") (pinfunction "V+_7") (pintype "power_in"))
      (node (ref "R59") (pin "1") (pinfunction "1_1") (pintype "passive"))
    )
    (net (code "96") (name "Net-(IC2-+IN)") (class "Default")
      (node (ref "IC2") (pin "3") (pinfunction "+IN_3") (pintype "input"))
      (node (ref "R5") (pin "2") (pinfunction "2_2") (pintype "passive"))
      (node (ref "R6") (pin "1") (pinfunction "1_1") (pintype "passive"))
    )
    (net (code "97") (name "Net-(IC2--IN)") (class "Default")
      (node (ref "C6") (pin "1") (pinfunction "1_1") (pintype "passive"))
      (node (ref "IC2") (pin "2") (pinfunction "-IN_2") (pintype "input"))
      (node (ref "R18") (pin "1") (pinfunction "1_1") (pintype "passive"))
    )
    (net (code "98") (name "Net-(IC2-OUT)") (class "Default")
      (node (ref "C6") (pin "2") (pinfunction "2_2") (pintype "passive"))
      (node (ref "IC2") (pin "6") (pinfunction "OUT_6") (pintype "output"))
      (node (ref "R7") (pin "1") (pinfunction "1_1") (pintype "passive"))
    )
    (net (code "99") (name "Net-(IC2-V-)") (class "Default")
      (node (ref "C40") (pin "2") (pinfunction "2_2") (pintype "passive"))
      (node (ref "IC2") (pin "4") (pinfunction "V-_4") (pintype "power_in"))
      (node (ref "R58") (pin "2") (pinfunction "2_2") (pintype "passive"))
    )
    (net (code "100") (name "Net-(IC3-+IN)") (class "Default")
      (node (ref "C38") (pin "2") (pinfunction "2_2") (pintype "passive"))
      (node (ref "IC3") (pin "3") (pinfunction "+IN_3") (pintype "input"))
      (node (ref "R24") (pin "2") (pinfunction "2_2") (pintype "passive"))
    )
    (net (code "101") (name "Net-(IC3--IN)") (class "Default")
      (node (ref "C50") (pin "1") (pinfunction "1_1") (pintype "passive"))
      (node (ref "IC3") (pin "2") (pinfunction "-IN_2") (pintype "input"))
      (node (ref "R22") (pin "2") (pinfunction "2_2") (pintype "passive"))
      (node (ref "R25") (pin "1") (pinfunction "1_1") (pintype "passive"))
    )
    (net (code "102") (name "Net-(IC3-OUT)") (class "Default")
      (node (ref "C50") (pin "2") (pinfunction "2_2") (pintype "passive"))
      (node (ref "IC3") (pin "6") (pinfunction "OUT_6") (pintype "output"))
      (node (ref "R19") (pin "1") (pinfunction "1_1") (pintype "passive"))
    )
    (net (code "103") (name "Net-(IC3-V+)") (class "Default")
      (node (ref "C39") (pin "1") (pinfunction "1_1") (pintype "passive"))
      (node (ref "IC3") (pin "7") (pinfunction "V+_7") (pintype "power_in"))
      (node (ref "R57") (pin "1") (pinfunction "1_1") (pintype "passive"))
    )
    (net (code "104") (name "Net-(IC4-+IN)") (class "Default")
      (node (ref "C32") (pin "2") (pinfunction "2_2") (pintype "passive"))
      (node (ref "IC4") (pin "3") (pinfunction "+IN_3") (pintype "input"))
      (node (ref "R37") (pin "2") (pinfunction "2_2") (pintype "passive"))
      (node (ref "R38") (pin "1") (pinfunction "1_1") (pintype "passive"))
    )
    (net (code "105") (name "Net-(IC4-V+)") (class "Default")
      (node (ref "C42") (pin "1") (pinfunction "1_1") (pintype "passive"))
      (node (ref "IC4") (pin "7") (pinfunction "V+_7") (pintype "power_in"))
      (node (ref "R60") (pin "1") (pinfunction "1_1") (pintype "passive"))
    )
    (net (code "106") (name "Net-(IC5-VIN)") (class "Default")
      (node (ref "C49") (pin "2") (pinfunction "2_2") (pintype "passive"))
      (node (ref "IC5") (pin "1") (pinfunction "VIN_1") (pintype "input"))
      (node (ref "R27") (pin "2") (pinfunction "2_2") (pintype "passive"))
    )
    (net (code "107") (name "Net-(LED1-C)") (class "Default")
      (node (ref "LED1") (pin "K") (pinfunction "C_K") (pintype "passive"))
      (node (ref "R63") (pin "1") (pinfunction "1_1") (pintype "passive"))
    )
    (net (code "108") (name "Net-(LED2-C)") (class "Default")
      (node (ref "LED2") (pin "K") (pinfunction "C_K") (pintype "passive"))
      (node (ref "R64") (pin "1") (pinfunction "1_1") (pintype "passive"))
    )
    (net (code "109") (name "Net-(LED5-PadC)") (class "Default")
      (node (ref "LED5") (pin "C") (pinfunction "C_C") (pintype "passive"))
      (node (ref "R31") (pin "1") (pinfunction "1_1") (pintype "passive"))
    )
    (net (code "110") (name "Net-(LED6-PadC)") (class "Default")
      (node (ref "LED6") (pin "C") (pinfunction "C_C") (pintype "passive"))
      (node (ref "R30") (pin "1") (pinfunction "1_1") (pintype "passive"))
    )
    (net (code "111") (name "Net-(LED7-C)") (class "Default")
      (node (ref "LED7") (pin "K") (pinfunction "C_K") (pintype "passive"))
      (node (ref "R65") (pin "1") (pinfunction "1_1") (pintype "passive"))
    )
    (net (code "112") (name "Net-(LED8-C)") (class "Default")
      (node (ref "LED8") (pin "K") (pinfunction "C_K") (pintype "passive"))
      (node (ref "R66") (pin "1") (pinfunction "1_1") (pintype "passive"))
    )
    (net (code "113") (name "Net-(LED9-C)") (class "Default")
      (node (ref "LED9") (pin "K") (pinfunction "C_K") (pintype "passive"))
      (node (ref "R67") (pin "1") (pinfunction "1_1") (pintype "passive"))
    )
    (net (code "114") (name "Net-(LED10-C)") (class "Default")
      (node (ref "LED10") (pin "K") (pinfunction "C_K") (pintype "passive"))
      (node (ref "R68") (pin "1") (pinfunction "1_1") (pintype "passive"))
    )
    (net (code "115") (name "Net-(LED11-C)") (class "Default")
      (node (ref "LED11") (pin "K") (pinfunction "C_K") (pintype "passive"))
      (node (ref "R69") (pin "1") (pinfunction "1_1") (pintype "passive"))
    )
    (net (code "116") (name "Net-(LED12-C)") (class "Default")
      (node (ref "LED12") (pin "K") (pinfunction "C_K") (pintype "passive"))
      (node (ref "R70") (pin "1") (pinfunction "1_1") (pintype "passive"))
    )
    (net (code "117") (name "Net-(LED13-C)") (class "Default")
      (node (ref "LED13") (pin "K") (pinfunction "C_K") (pintype "passive"))
      (node (ref "R71") (pin "1") (pinfunction "1_1") (pintype "passive"))
    )
    (net (code "118") (name "Net-(LED14-C)") (class "Default")
      (node (ref "LED14") (pin "K") (pinfunction "C_K") (pintype "passive"))
      (node (ref "R72") (pin "1") (pinfunction "1_1") (pintype "passive"))
    )
    (net (code "119") (name "Net-(LED15-C)") (class "Default")
      (node (ref "LED15") (pin "K") (pinfunction "C_K") (pintype "passive"))
      (node (ref "R73") (pin "1") (pinfunction "1_1") (pintype "passive"))
    )
    (net (code "120") (name "Net-(LED16-C)") (class "Default")
      (node (ref "LED16") (pin "K") (pinfunction "C_K") (pintype "passive"))
      (node (ref "R74") (pin "1") (pinfunction "1_1") (pintype "passive"))
    )
    (net (code "121") (name "Net-(OSC1-P$1)") (class "Default")
      (node (ref "C12") (pin "1") (pinfunction "1_1") (pintype "passive"))
      (node (ref "OSC1") (pin "1") (pinfunction "P$1_1") (pintype "bidirectional"))
      (node (ref "U1") (pin "12") (pinfunction "OSC_IN_12") (pintype "input"))
    )
    (net (code "122") (name "Net-(OSC1-P$2)") (class "Default")
      (node (ref "C13") (pin "1") (pinfunction "1_1") (pintype "passive"))
      (node (ref "OSC1") (pin "3") (pinfunction "P$2_3") (pintype "bidirectional"))
      (node (ref "R62") (pin "1") (pinfunction "1_1") (pintype "passive"))
    )
    (net (code "123") (name "Net-(Q1-D)") (class "Default")
      (node (ref "Q1") (pin "3") (pinfunction "D_3") (pintype "passive"))
      (node (ref "R5") (pin "1") (pinfunction "1_1") (pintype "passive"))
    )
    (net (code "124") (name "Net-(Q1-G)") (class "Default")
      (node (ref "Q1") (pin "1") (pinfunction "G_1") (pintype "passive"))
      (node (ref "R2") (pin "2") (pinfunction "2_2") (pintype "passive"))
    )
    (net (code "125") (name "Net-(Q1-S)") (class "Default")
      (node (ref "Q1") (pin "2") (pinfunction "S_2") (pintype "passive"))
      (node (ref "R3") (pin "2") (pinfunction "2_2") (pintype "passive"))
      (node (ref "R4") (pin "2") (pinfunction "2_2") (pintype "passive"))
    )
    (net (code "126") (name "Net-(Q2-G)") (class "Default")
      (node (ref "Q2") (pin "1") (pinfunction "G_1") (pintype "passive"))
      (node (ref "R7") (pin "2") (pinfunction "2_2") (pintype "passive"))
    )
    (net (code "127") (name "Net-(Q2-S)") (class "Default")
      (node (ref "Q2") (pin "3") (pinfunction "S_3") (pintype "passive"))
      (node (ref "R18") (pin "2") (pinfunction "2_2") (pintype "passive"))
      (node (ref "R20") (pin "1") (pinfunction "1_1") (pintype "passive"))
    )
    (net (code "128") (name "Net-(Q3-PadE)") (class "Default")
      (node (ref "Q3") (pin "E") (pinfunction "E_E") (pintype "passive"))
      (node (ref "R26") (pin "2") (pinfunction "2_2") (pintype "passive"))
      (node (ref "R28") (pin "1") (pinfunction "1_1") (pintype "passive"))
      (node (ref "R33") (pin "1") (pinfunction "1_1") (pintype "passive"))
    )
    (net (code "129") (name "Net-(Q5-PadE)") (class "Default")
      (node (ref "Q5") (pin "E") (pinfunction "E_E") (pintype "passive"))
      (node (ref "R76") (pin "1") (pinfunction "1_1") (pintype "passive"))
      (node (ref "R77") (pin "2") (pinfunction "2_2") (pintype "passive"))
      (node (ref "R82") (pin "1") (pinfunction "1_1") (pintype "passive"))
    )
    (net (code "130") (name "Net-(R15-Pad1)") (class "Default")
      (node (ref "R15") (pin "1") (pinfunction "1_1") (pintype "passive"))
      (node (ref "S1") (pin "1") (pinfunction "1_1") (pintype "passive"))
    )
    (net (code "131") (name "Net-(R16-Pad2)") (class "Default")
      (node (ref "R16") (pin "2") (pinfunction "2_2") (pintype "passive"))
      (node (ref "S1") (pin "3") (pinfunction "3_3") (pintype "passive"))
    )
    (net (code "132") (name "Net-(R17-Pad2)") (class "Default")
      (node (ref "R17") (pin "2") (pinfunction "2_2") (pintype "passive"))
      (node (ref "S1") (pin "5") (pinfunction "5_5") (pintype "passive"))
    )
    (net (code "133") (name "Net-(R20-Pad2)") (class "Default")
      (node (ref "R20") (pin "2") (pinfunction "2_2") (pintype "passive"))
      (node (ref "R51") (pin "1") (pinfunction "1_1") (pintype "passive"))
      (node (ref "R53") (pin "1") (pinfunction "1_1") (pintype "passive"))
    )
    (net (code "134") (name "Net-(R23-Pad2)") (class "Default")
      (node (ref "R23") (pin "2") (pinfunction "2_2") (pintype "passive"))
      (node (ref "T2") (pin "2") (pinfunction "C_2") (pintype "passive"))
      (node (ref "T2") (pin "4") (pinfunction "C_4") (pintype "passive"))
    )
    (net (code "135") (name "Net-(R50-Pad1)") (class "Default")
      (node (ref "R50") (pin "1") (pinfunction "1_1") (pintype "passive"))
      (node (ref "R53") (pin "2") (pinfunction "2_2") (pintype "passive"))
      (node (ref "R6") (pin "2") (pinfunction "2_2") (pintype "passive"))
      (node (ref "R61") (pin "1") (pinfunction "1_1") (pintype "passive"))
    )
    (net (code "136") (name "Net-(T1-C)") (class "Default")
      (node (ref "Q4") (pin "B") (pinfunction "B_B") (pintype "passive"))
      (node (ref "R8") (pin "2") (pinfunction "2_2") (pintype "passive"))
      (node (ref "T1") (pin "3") (pinfunction "C_3") (pintype "passive"))
    )
    (net (code "137") (name "Net-(T2-B)") (class "Default")
      (node (ref "Q3") (pin "C") (pinfunction "C_C") (pintype "passive"))
      (node (ref "R19") (pin "2") (pinfunction "2_2") (pintype "passive"))
      (node (ref "T2") (pin "1") (pinfunction "B_1") (pintype "passive"))
    )
    (net (code "138") (name "Net-(T2-E)") (class "Default")
      (node (ref "Q3") (pin "B") (pinfunction "B_B") (pintype "passive"))
      (node (ref "R26") (pin "1") (pinfunction "1_1") (pintype "passive"))
      (node (ref "T2") (pin "3") (pinfunction "E_3") (pintype "passive"))
    )
    (net (code "139") (name "Net-(T3-C)") (class "Default")
      (node (ref "Q5") (pin "B") (pinfunction "B_B") (pintype "passive"))
      (node (ref "R76") (pin "2") (pinfunction "2_2") (pintype "passive"))
      (node (ref "T3") (pin "3") (pinfunction "C_3") (pintype "passive"))
    )
    (net (code "140") (name "Net-(T4-C)") (class "Default")
      (node (ref "Q6") (pin "B") (pinfunction "B_B") (pintype "passive"))
      (node (ref "R79") (pin "2") (pinfunction "2_2") (pintype "passive"))
      (node (ref "T4") (pin "3") (pinfunction "C_3") (pintype "passive"))
    )
    (net (code "141") (name "Net-(U1L-OSC_OUT)") (class "Default")
      (node (ref "R62") (pin "2") (pinfunction "2_2") (pintype "passive"))
      (node (ref "U1") (pin "13") (pinfunction "OSC_OUT_13") (pintype "output"))
    )
    (net (code "142") (name "Net-(U1M-BOOT0)") (class "Default")
      (node (ref "R11") (pin "2") (pinfunction "2_2") (pintype "passive"))
      (node (ref "U1") (pin "94") (pinfunction "BOOT0_94") (pintype "input"))
    )
    (net (code "143") (name "Net-(U1N-VDDA)") (class "Default")
      (node (ref "C11") (pin "1") (pinfunction "1_1") (pintype "passive"))
      (node (ref "C14") (pin "1") (pinfunction "1_1") (pintype "passive"))
      (node (ref "L1") (pin "1") (pinfunction "1_1") (pintype "passive"))
      (node (ref "U1") (pin "22") (pinfunction "VDDA_22") (pintype "power_in"))
    )
    (net (code "144") (name "Net-(U1N-VLCD)") (class "Default")
      (node (ref "C15") (pin "1") (pinfunction "1_1") (pintype "passive"))
      (node (ref "U1") (pin "6") (pinfunction "VLCD_6") (pintype "power_in"))
    )
    (net (code "145") (name "Net-(U3-+VIN)") (class "Default")
      (node (ref "C30") (pin "1") (pinfunction "1_1") (pintype "passive"))
      (node (ref "L3") (pin "2") (pinfunction "2_2") (pintype "passive"))
      (node (ref "U3") (pin "1") (pinfunction "+VIN_1") (pintype "bidirectional"))
    )
    (net (code "146") (name "Net-(U4-IN+)") (class "Default")
      (node (ref "C34") (pin "1") (pinfunction "1_1") (pintype "passive"))
      (node (ref "R50") (pin "2") (pinfunction "2_2") (pintype "passive"))
      (node (ref "U4") (pin "4") (pinfunction "IN+_4") (pintype "bidirectional"))
    )
    (net (code "147") (name "Net-(U4-IN-)") (class "Default")
      (node (ref "C34") (pin "2") (pinfunction "2_2") (pintype "passive"))
      (node (ref "R51") (pin "2") (pinfunction "2_2") (pintype "passive"))
      (node (ref "U4") (pin "5") (pinfunction "IN-_5") (pintype "bidirectional"))
    )
    (net (code "148") (name "Net-(U4-OUT)") (class "Default")
      (node (ref "R52") (pin "1") (pinfunction "1_1") (pintype "passive"))
      (node (ref "U4") (pin "6") (pinfunction "OUT_6") (pintype "bidirectional"))
    )
    (net (code "149") (name "Net-(U4-VS)") (class "Default")
      (node (ref "C35") (pin "1") (pinfunction "1_1") (pintype "passive"))
      (node (ref "R54") (pin "1") (pinfunction "1_1") (pintype "passive"))
      (node (ref "U4") (pin "3") (pinfunction "VS_3") (pintype "bidirectional"))
    )
    (net (code "150") (name "Net-(U5-IN+)") (class "Default")
      (node (ref "C24") (pin "1") (pinfunction "1_1") (pintype "passive"))
      (node (ref "D7") (pin "C") (pinfunction "C_C") (pintype "passive"))
      (node (ref "R29") (pin "2") (pinfunction "2_2") (pintype "passive"))
      (node (ref "U5") (pin "4") (pinfunction "IN+_4") (pintype "bidirectional"))
    )
    (net (code "151") (name "Net-(U5-IN-)") (class "Default")
      (node (ref "C24") (pin "2") (pinfunction "2_2") (pintype "passive"))
      (node (ref "D8") (pin "C") (pinfunction "C_C") (pintype "passive"))
      (node (ref "R33") (pin "2") (pinfunction "2_2") (pintype "passive"))
      (node (ref "U5") (pin "5") (pinfunction "IN-_5") (pintype "bidirectional"))
    )
    (net (code "152") (name "Net-(U5-OUT)") (class "Default")
      (node (ref "R34") (pin "1") (pinfunction "1_1") (pintype "passive"))
      (node (ref "U5") (pin "6") (pinfunction "OUT_6") (pintype "bidirectional"))
    )
    (net (code "153") (name "Net-(U5-VS)") (class "Default")
      (node (ref "C36") (pin "1") (pinfunction "1_1") (pintype "passive"))
      (node (ref "R55") (pin "1") (pinfunction "1_1") (pintype "passive"))
      (node (ref "U5") (pin "3") (pinfunction "VS_3") (pintype "bidirectional"))
    )
    (net (code "154") (name "Net-(U6-IN+)") (class "Default")
      (node (ref "C26") (pin "1") (pinfunction "1_1") (pintype "passive"))
      (node (ref "D5") (pin "C") (pinfunction "C_C") (pintype "passive"))
      (node (ref "R41") (pin "2") (pinfunction "2_2") (pintype "passive"))
      (node (ref "U6") (pin "4") (pinfunction "IN+_4") (pintype "bidirectional"))
    )
    (net (code "155") (name "Net-(U6-IN-)") (class "Default")
      (node (ref "C26") (pin "2") (pinfunction "2_2") (pintype "passive"))
      (node (ref "D6") (pin "C") (pinfunction "C_C") (pintype "passive"))
      (node (ref "R42") (pin "2") (pinfunction "2_2") (pintype "passive"))
      (node (ref "U6") (pin "5") (pinfunction "IN-_5") (pintype "bidirectional"))
    )
    (net (code "156") (name "Net-(U6-OUT)") (class "Default")
      (node (ref "R43") (pin "1") (pinfunction "1_1") (pintype "passive"))
      (node (ref "U6") (pin "6") (pinfunction "OUT_6") (pintype "bidirectional"))
    )
    (net (code "157") (name "Net-(U6-VS)") (class "Default")
      (node (ref "C37") (pin "1") (pinfunction "1_1") (pintype "passive"))
      (node (ref "R56") (pin "1") (pinfunction "1_1") (pintype "passive"))
      (node (ref "U6") (pin "3") (pinfunction "VS_3") (pintype "bidirectional"))
    )
    (net (code "158") (name "Net-(U7-+VIN)") (class "Default")
      (node (ref "C18") (pin "1") (pinfunction "1_1") (pintype "passive"))
      (node (ref "C20") (pin "1") (pinfunction "1_1") (pintype "passive"))
      (node (ref "C21") (pin "+") (pinfunction "+_+") (pintype "passive"))
      (node (ref "D2") (pin "C") (pinfunction "C_C") (pintype "passive"))
      (node (ref "L2") (pin "2") (pinfunction "2_2") (pintype "passive"))
      (node (ref "L4") (pin "1") (pinfunction "1_1") (pintype "passive"))
      (node (ref "U7") (pin "VIN+") (pinfunction "+VIN_VIN+") (pintype "bidirectional"))
    )
    (net (code "159") (name "Net-(U7-+VOUT)") (class "Default")
      (node (ref "R1") (pin "1") (pinfunction "1_1") (pintype "passive"))
      (node (ref "U7") (pin "VOUT+") (pinfunction "+VOUT_VOUT+") (pintype "bidirectional"))
    )
    (net (code "160") (name "Net-(U30-A)") (class "Default")
      (node (ref "R13") (pin "2") (pinfunction "2_2") (pintype "passive"))
      (node (ref "U30") (pin "12") (pinfunction "A_12") (pintype "input"))
    )
    (net (code "161") (name "Net-(U30-B)") (class "Default")
      (node (ref "R14") (pin "2") (pinfunction "2_2") (pintype "passive"))
      (node (ref "U30") (pin "13") (pinfunction "B_13") (pintype "input"))
    )
    (net (code "162") (name "Net-(U30-VCC1)") (class "Default")
      (node (ref "C17") (pin "1") (pinfunction "1_1") (pintype "passive"))
      (node (ref "R49") (pin "1") (pinfunction "1_1") (pintype "passive"))
      (node (ref "U30") (pin "1") (pinfunction "VCC1_1") (pintype "input"))
    )
    (net (code "163") (name "Net-(U31-+VIN)") (class "Default")
      (node (ref "C19") (pin "1") (pinfunction "1_1") (pintype "passive"))
      (node (ref "L4") (pin "2") (pinfunction "2_2") (pintype "passive"))
      (node (ref "U31") (pin "1") (pinfunction "+VIN_1") (pintype "bidirectional"))
    )
    (net (code "164") (name "OT_CONTROLLER") (class "Default")
      (node (ref "D14") (pin "1") (pinfunction "A_1") (pintype "passive"))
      (node (ref "PL2") (pin "3") (pinfunction "S_3") (pintype "passive"))
      (node (ref "PL2") (pin "4") (pinfunction "S_4") (pintype "passive"))
      (node (ref "R25") (pin "2") (pinfunction "2_2") (pintype "passive"))
      (node (ref "R36") (pin "2") (pinfunction "2_2") (pintype "passive"))
      (node (ref "R78") (pin "2") (pinfunction "2_2") (pintype "passive"))
    )
    (net (code "165") (name "OT_MONITOR_L") (class "Default")
      (node (ref "PL1") (pin "3") (pinfunction "S_3") (pintype "passive"))
      (node (ref "R40") (pin "1") (pinfunction "1_1") (pintype "passive"))
      (node (ref "R42") (pin "1") (pinfunction "1_1") (pintype "passive"))
    )
    (net (code "166") (name "OT_MONITOR_R") (class "Default")
      (node (ref "PL1") (pin "4") (pinfunction "S_4") (pintype "passive"))
      (node (ref "R40") (pin "2") (pinfunction "2_2") (pintype "passive"))
      (node (ref "R41") (pin "1") (pinfunction "1_1") (pintype "passive"))
      (node (ref "R45") (pin "2") (pinfunction "2_2") (pintype "passive"))
      (node (ref "R75") (pin "2") (pinfunction "2_2") (pintype "passive"))
    )
    (net (code "167") (name "OT_THERMOSTAT") (class "Default")
      (node (ref "D4") (pin "3") (pinfunction "C_3") (pintype "passive"))
      (node (ref "PL3") (pin "3") (pinfunction "S_3") (pintype "passive"))
      (node (ref "PL3") (pin "4") (pinfunction "S_4") (pintype "passive"))
      (node (ref "R48") (pin "2") (pinfunction "2_2") (pintype "passive"))
      (node (ref "R81") (pin "2") (pinfunction "2_2") (pintype "passive"))
    )
    (net (code "168") (name "POLARITY_CONTROLLER") (class "Default")
      (node (ref "R82") (pin "2") (pinfunction "2_2") (pintype "passive"))
      (node (ref "U1") (pin "5") (pinfunction "PE6_5") (pintype "bidirectional"))
    )
    (net (code "169") (name "POLARITY_MONITOR") (class "Default")
      (node (ref "Q4") (pin "E") (pinfunction "E_E") (pintype "passive"))
      (node (ref "R8") (pin "1") (pinfunction "1_1") (pintype "passive"))
      (node (ref "R9") (pin "2") (pinfunction "2_2") (pintype "passive"))
      (node (ref "U1") (pin "92") (pinfunction "PB6_92") (pintype "bidirectional"))
    )
    (net (code "170") (name "POLARITY_THERMOSTAT") (class "Default")
      (node (ref "Q6") (pin "E") (pinfunction "E_E") (pintype "passive"))
      (node (ref "R79") (pin "1") (pinfunction "1_1") (pintype "passive"))
      (node (ref "R80") (pin "2") (pinfunction "2_2") (pintype "passive"))
      (node (ref "U1") (pin "42") (pinfunction "PE11_42") (pintype "bidirectional"))
    )
    (net (code "171") (name "SPI1_CS") (class "Default")
      (node (ref "U1") (pin "43") (pinfunction "PE12_43") (pintype "bidirectional"))
    )
    (net (code "172") (name "SPI1_MISO") (class "Default")
      (node (ref "U1") (pin "45") (pinfunction "PE14_45") (pintype "bidirectional"))
    )
    (net (code "173") (name "SPI1_MOSI") (class "Default")
      (node (ref "U1") (pin "46") (pinfunction "PE15_46") (pintype "bidirectional"))
    )
    (net (code "174") (name "SPI1_SCLK") (class "Default")
      (node (ref "U1") (pin "44") (pinfunction "PE13_44") (pintype "bidirectional"))
    )
    (net (code "175") (name "SWCLK") (class "Default")
      (node (ref "K1") (pin "4") (pinfunction "SWDCLK/TCK_4") (pintype "bidirectional"))
      (node (ref "U1") (pin "76") (pinfunction "PA14_76") (pintype "bidirectional"))
    )
    (net (code "176") (name "SWDIO") (class "Default")
      (node (ref "K1") (pin "2") (pinfunction "SWDIO/TMS_2") (pintype "bidirectional"))
      (node (ref "U1") (pin "72") (pinfunction "PA13_72") (pintype "bidirectional"))
    )
    (net (code "177") (name "USART2_DE") (class "Default")
      (node (ref "R32") (pin "2") (pinfunction "2_2") (pintype "passive"))
      (node (ref "U1") (pin "85") (pinfunction "PD4_85") (pintype "bidirectional"))
      (node (ref "U30") (pin "4") (pinfunction "~{RE}_4") (pintype "input"))
      (node (ref "U30") (pin "5") (pinfunction "DE_5") (pintype "input"))
    )
    (net (code "178") (name "USART2_RXD") (class "Default")
      (node (ref "R31") (pin "2") (pinfunction "2_2") (pintype "passive"))
      (node (ref "U1") (pin "87") (pinfunction "PD6_87") (pintype "bidirectional"))
      (node (ref "U30") (pin "3") (pinfunction "R_3") (pintype "input"))
    )
    (net (code "179") (name "USART2_TXD") (class "Default")
      (node (ref "R30") (pin "2") (pinfunction "2_2") (pintype "passive"))
      (node (ref "U1") (pin "86") (pinfunction "PD5_86") (pintype "bidirectional"))
      (node (ref "U30") (pin "6") (pinfunction "D_6") (pintype "input"))
    )
    (net (code "180") (name "VCC") (class "Default")
      (node (ref "C65") (pin "1") (pinfunction "1_1") (pintype "passive"))
      (node (ref "C66") (pin "+") (pinfunction "+_+") (pintype "passive"))
      (node (ref "C68") (pin "1") (pinfunction "1_1") (pintype "passive"))
      (node (ref "R10") (pin "2") (pinfunction "2_2") (pintype "passive"))
      (node (ref "R15") (pin "2") (pinfunction "2_2") (pintype "passive"))
      (node (ref "U30") (pin "16") (pinfunction "VCC2_16") (pintype "input"))
      (node (ref "U31") (pin "3") (pinfunction "+VOUT_3") (pintype "bidirectional"))
    )
    (net (code "181") (name "VREF") (class "Default")
      (node (ref "C47") (pin "1") (pinfunction "1_1") (pintype "passive"))
      (node (ref "C48") (pin "1") (pinfunction "1_1") (pintype "passive"))
      (node (ref "C51") (pin "1") (pinfunction "1_1") (pintype "passive"))
      (node (ref "C52") (pin "1") (pinfunction "1_1") (pintype "passive"))
      (node (ref "C53") (pin "2") (pinfunction "2_2") (pintype "passive"))
      (node (ref "IC5") (pin "2") (pinfunction "VO_2") (pintype "output"))
      (node (ref "R38") (pin "2") (pinfunction "2_2") (pintype "passive"))
      (node (ref "R46") (pin "2") (pinfunction "2_2") (pintype "passive"))
      (node (ref "U1") (pin "21") (pinfunction "VREF+_21") (pintype "power_in"))
      (node (ref "ZD1") (pin "1") (pinfunction "R_1") (pintype "passive"))
      (node (ref "ZD1") (pin "3") (pinfunction "C_3") (pintype "passive"))
    )
    (net (code "182") (name "VREF{slash}2") (class "Default")
      (node (ref "IC4") (pin "2") (pinfunction "-IN_2") (pintype "input"))
      (node (ref "IC4") (pin "6") (pinfunction "OUT_6") (pintype "output"))
      (node (ref "U6") (pin "1") (pinfunction "REF_1") (pintype "bidirectional"))
    )
    (net (code "183") (name "unconnected-(K1-KEY-Pad7)") (class "Default")
      (node (ref "K1") (pin "7") (pinfunction "KEY_7") (pintype "bidirectional"))
    )
    (net (code "184") (name "unconnected-(K1-NC{slash}TDI-Pad8)") (class "Default")
      (node (ref "K1") (pin "8") (pinfunction "NC/TDI_8") (pintype "bidirectional"))
    )
    (net (code "185") (name "unconnected-(K1-SWO{slash}TDO-Pad6)") (class "Default")
      (node (ref "K1") (pin "6") (pinfunction "SWO/TDO_6") (pintype "bidirectional"))
    )
    (net (code "186") (name "unconnected-(SW1-1A-Pad2)") (class "Default")
      (node (ref "SW1") (pin "2") (pinfunction "1A_2") (pintype "passive"))
    )
    (net (code "187") (name "unconnected-(SW1-2A-Pad4)") (class "Default")
      (node (ref "SW1") (pin "4") (pinfunction "2A_4") (pintype "passive"))
    )
    (net (code "188") (name "unconnected-(U1A-PA0-Pad23)") (class "Default")
      (node (ref "U1") (pin "23") (pinfunction "PA0_23") (pintype "bidirectional"))
    )
    (net (code "189") (name "unconnected-(U1A-PA1-Pad24)") (class "Default")
      (node (ref "U1") (pin "24") (pinfunction "PA1_24") (pintype "bidirectional"))
    )
    (net (code "190") (name "unconnected-(U1B-PA8-Pad67)") (class "Default")
      (node (ref "U1") (pin "67") (pinfunction "PA8_67") (pintype "bidirectional"))
    )
    (net (code "191") (name "unconnected-(U1B-PA9-Pad68)") (class "Default")
      (node (ref "U1") (pin "68") (pinfunction "PA9_68") (pintype "bidirectional"))
    )
    (net (code "192") (name "unconnected-(U1B-PA10-Pad69)") (class "Default")
      (node (ref "U1") (pin "69") (pinfunction "PA10_69") (pintype "bidirectional"))
    )
    (net (code "193") (name "unconnected-(U1B-PA11-Pad70)") (class "Default")
      (node (ref "U1") (pin "70") (pinfunction "PA11_70") (pintype "bidirectional"))
    )
    (net (code "194") (name "unconnected-(U1B-PA12-Pad71)") (class "Default")
      (node (ref "U1") (pin "71") (pinfunction "PA12_71") (pintype "bidirectional"))
    )
    (net (code "195") (name "unconnected-(U1B-PA15-Pad77)") (class "Default")
      (node (ref "U1") (pin "77") (pinfunction "PA15_77") (pintype "bidirectional"))
    )
    (net (code "196") (name "unconnected-(U1C-PB2-Pad37)") (class "Default")
      (node (ref "U1") (pin "37") (pinfunction "PB2_37") (pintype "bidirectional"))
    )
    (net (code "197") (name "unconnected-(U1C-PB7-Pad93)") (class "Default")
      (node (ref "U1") (pin "93") (pinfunction "PB7_93") (pintype "bidirectional"))
    )
    (net (code "198") (name "unconnected-(U1D-PB8-Pad95)") (class "Default")
      (node (ref "U1") (pin "95") (pinfunction "PB8_95") (pintype "bidirectional"))
    )
    (net (code "199") (name "unconnected-(U1D-PB9-Pad96)") (class "Default")
      (node (ref "U1") (pin "96") (pinfunction "PB9_96") (pintype "bidirectional"))
    )
    (net (code "200") (name "unconnected-(U1D-PB10-Pad47)") (class "Default")
      (node (ref "U1") (pin "47") (pinfunction "PB10_47") (pintype "bidirectional"))
    )
    (net (code "201") (name "unconnected-(U1D-PB11-Pad48)") (class "Default")
      (node (ref "U1") (pin "48") (pinfunction "PB11_48") (pintype "bidirectional"))
    )
    (net (code "202") (name "unconnected-(U1D-PB12-Pad51)") (class "Default")
      (node (ref "U1") (pin "51") (pinfunction "PB12_51") (pintype "bidirectional"))
    )
    (net (code "203") (name "unconnected-(U1D-PB13-Pad52)") (class "Default")
      (node (ref "U1") (pin "52") (pinfunction "PB13_52") (pintype "bidirectional"))
    )
    (net (code "204") (name "unconnected-(U1D-PB14-Pad53)") (class "Default")
      (node (ref "U1") (pin "53") (pinfunction "PB14_53") (pintype "bidirectional"))
    )
    (net (code "205") (name "unconnected-(U1D-PB15-Pad54)") (class "Default")
      (node (ref "U1") (pin "54") (pinfunction "PB15_54") (pintype "bidirectional"))
    )
    (net (code "206") (name "unconnected-(U1E-PC2-Pad17)") (class "Default")
      (node (ref "U1") (pin "17") (pinfunction "PC2_17") (pintype "bidirectional"))
    )
    (net (code "207") (name "unconnected-(U1E-PC3-Pad18)") (class "Default")
      (node (ref "U1") (pin "18") (pinfunction "PC3_18") (pintype "bidirectional"))
    )
    (net (code "208") (name "unconnected-(U1E-PC6-Pad63)") (class "Default")
      (node (ref "U1") (pin "63") (pinfunction "PC6_63") (pintype "bidirectional"))
    )
    (net (code "209") (name "unconnected-(U1E-PC7-Pad64)") (class "Default")
      (node (ref "U1") (pin "64") (pinfunction "PC7_64") (pintype "bidirectional"))
    )
    (net (code "210") (name "unconnected-(U1F-PC8-Pad65)") (class "Default")
      (node (ref "U1") (pin "65") (pinfunction "PC8_65") (pintype "bidirectional"))
    )
    (net (code "211") (name "unconnected-(U1F-PC9-Pad66)") (class "Default")
      (node (ref "U1") (pin "66") (pinfunction "PC9_66") (pintype "bidirectional"))
    )
    (net (code "212") (name "unconnected-(U1F-PC10-Pad78)") (class "Default")
      (node (ref "U1") (pin "78") (pinfunction "PC10_78") (pintype "bidirectional"))
    )
    (net (code "213") (name "unconnected-(U1F-PC11-Pad79)") (class "Default")
      (node (ref "U1") (pin "79") (pinfunction "PC11_79") (pintype "bidirectional"))
    )
    (net (code "214") (name "unconnected-(U1F-PC12-Pad80)") (class "Default")
      (node (ref "U1") (pin "80") (pinfunction "PC12_80") (pintype "bidirectional"))
    )
    (net (code "215") (name "unconnected-(U1F-PC13-Pad7)") (class "Default")
      (node (ref "U1") (pin "7") (pinfunction "PC13_7") (pintype "bidirectional"))
    )
    (net (code "216") (name "unconnected-(U1F-PC14-Pad8)") (class "Default")
      (node (ref "U1") (pin "8") (pinfunction "PC14_8") (pintype "bidirectional"))
    )
    (net (code "217") (name "unconnected-(U1F-PC15-Pad9)") (class "Default")
      (node (ref "U1") (pin "9") (pinfunction "PC15_9") (pintype "bidirectional"))
    )
    (net (code "218") (name "unconnected-(U1G-PD0-Pad81)") (class "Default")
      (node (ref "U1") (pin "81") (pinfunction "PD0_81") (pintype "bidirectional"))
    )
    (net (code "219") (name "unconnected-(U1G-PD1-Pad82)") (class "Default")
      (node (ref "U1") (pin "82") (pinfunction "PD1_82") (pintype "bidirectional"))
    )
    (net (code "220") (name "unconnected-(U1G-PD2-Pad83)") (class "Default")
      (node (ref "U1") (pin "83") (pinfunction "PD2_83") (pintype "bidirectional"))
    )
    (net (code "221") (name "unconnected-(U1G-PD3-Pad84)") (class "Default")
      (node (ref "U1") (pin "84") (pinfunction "PD3_84") (pintype "bidirectional"))
    )
    (net (code "222") (name "unconnected-(U1H-PD8-Pad55)") (class "Default")
      (node (ref "U1") (pin "55") (pinfunction "PD8_55") (pintype "bidirectional"))
    )
    (net (code "223") (name "unconnected-(U1H-PD9-Pad56)") (class "Default")
      (node (ref "U1") (pin "56") (pinfunction "PD9_56") (pintype "bidirectional"))
    )
    (net (code "224") (name "unconnected-(U1H-PD10-Pad57)") (class "Default")
      (node (ref "U1") (pin "57") (pinfunction "PD10_57") (pintype "bidirectional"))
    )
    (net (code "225") (name "unconnected-(U1H-PD11-Pad58)") (class "Default")
      (node (ref "U1") (pin "58") (pinfunction "PD11_58") (pintype "bidirectional"))
    )
    (net (code "226") (name "unconnected-(U1I-PE0-Pad97)") (class "Default")
      (node (ref "U1") (pin "97") (pinfunction "PE0_97") (pintype "bidirectional"))
    )
    (net (code "227") (name "unconnected-(U1I-PE1-Pad98)") (class "Default")
      (node (ref "U1") (pin "98") (pinfunction "PE1_98") (pintype "bidirectional"))
    )
    (net (code "228") (name "unconnected-(U1I-PE7-Pad38)") (class "Default")
      (node (ref "U1") (pin "38") (pinfunction "PE7_38") (pintype "bidirectional"))
    )
    (net (code "229") (name "unconnected-(U1J-PE10-Pad41)") (class "Default")
      (node (ref "U1") (pin "41") (pinfunction "PE10_41") (pintype "bidirectional"))
    )
    (net (code "230") (name "unconnected-(U1K-PH9-Pad10)") (class "Default")
      (node (ref "U1") (pin "10") (pinfunction "PH9_10") (pintype "bidirectional"))
    )
    (net (code "231") (name "unconnected-(U1K-PH10-Pad11)") (class "Default")
      (node (ref "U1") (pin "11") (pinfunction "PH10_11") (pintype "bidirectional"))
    )
    (net (code "232") (name "unconnected-(U30-NC-Pad11)") (class "Default")
      (node (ref "U30") (pin "11") (pinfunction "NC_11") (pintype "input"))
    )
    (net (code "233") (name "unconnected-(U30-NC-Pad14)") (class "Default")
      (node (ref "U30") (pin "14") (pinfunction "NC_14") (pintype "input"))
    )
  )
)
